# driver_board_v7.net
KiCad netlist of a schematic drawn in EAGLE
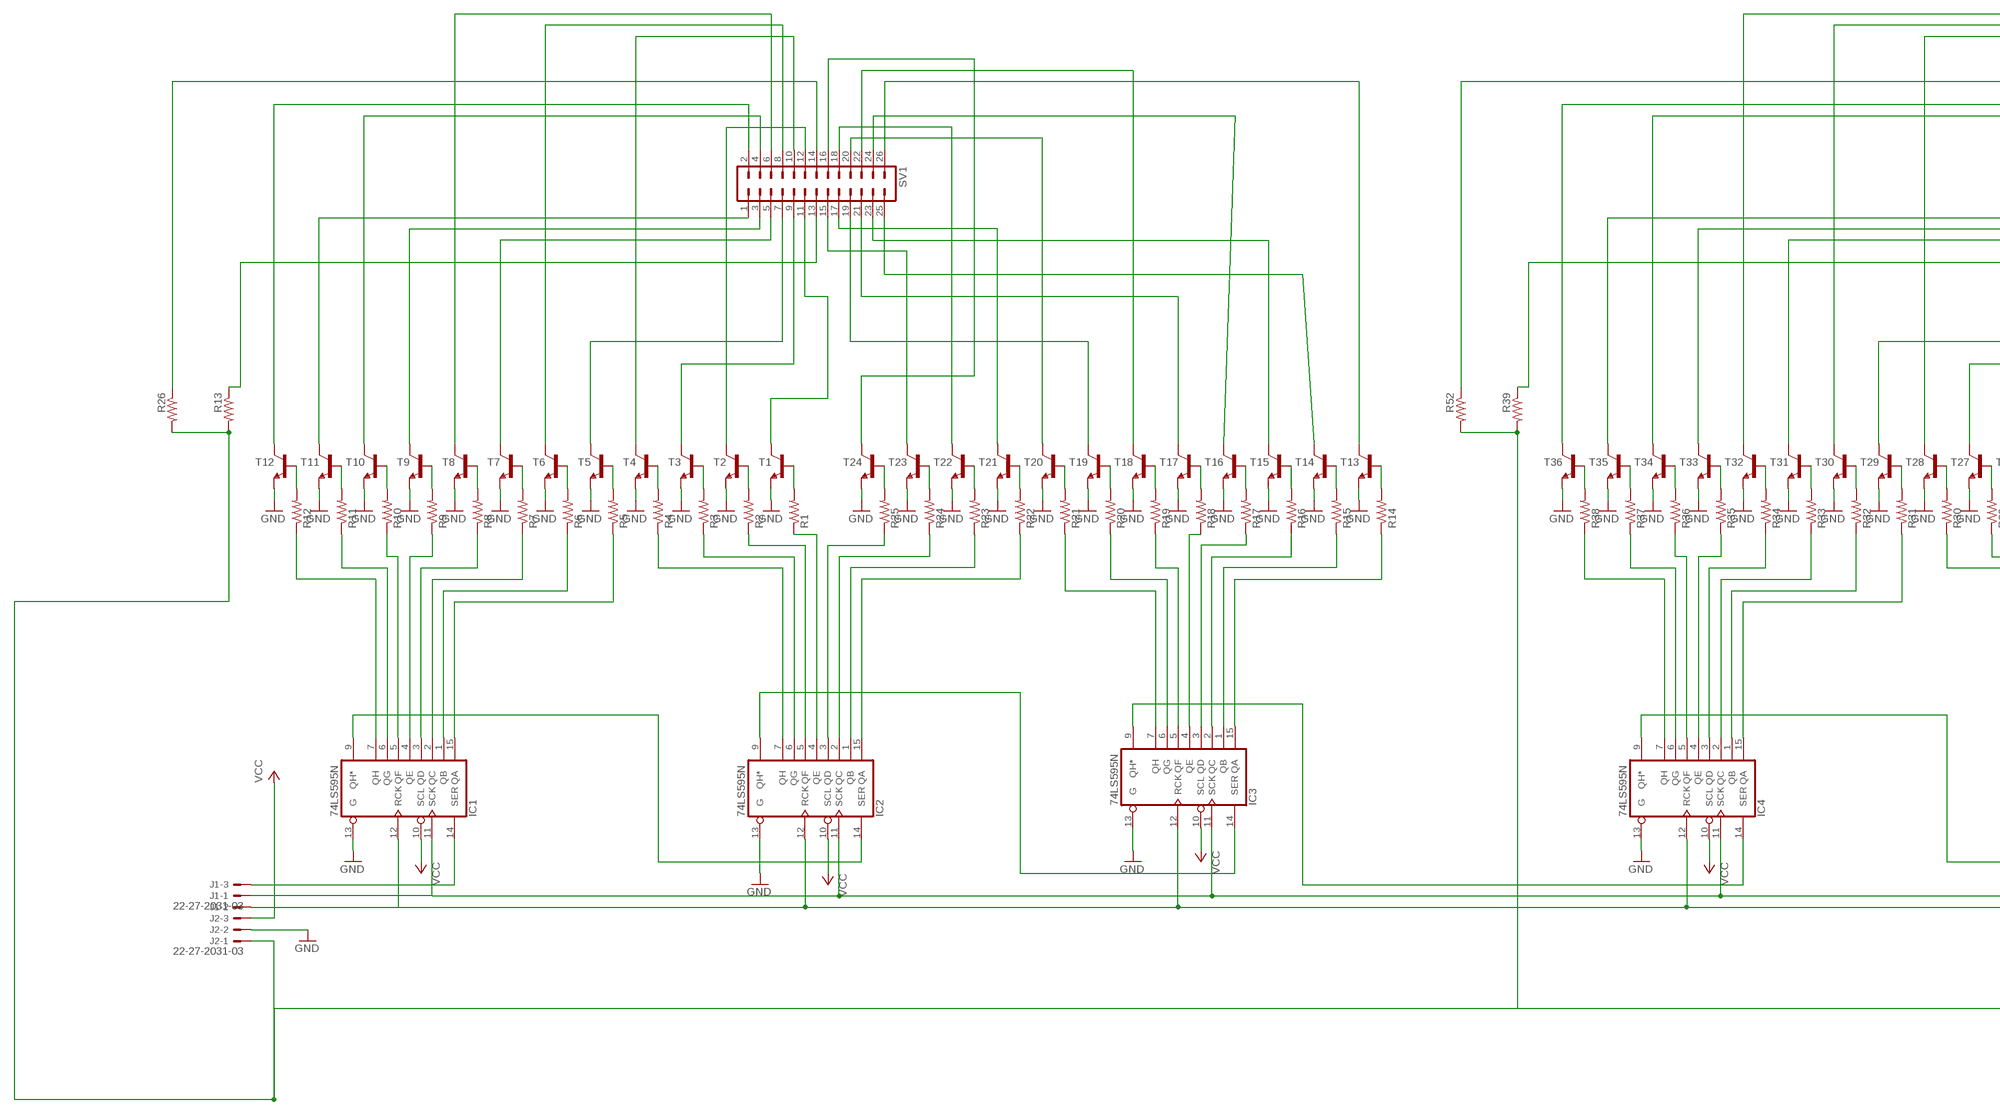
[diagram p0: schematic, sheet 1, part 1 of 2]
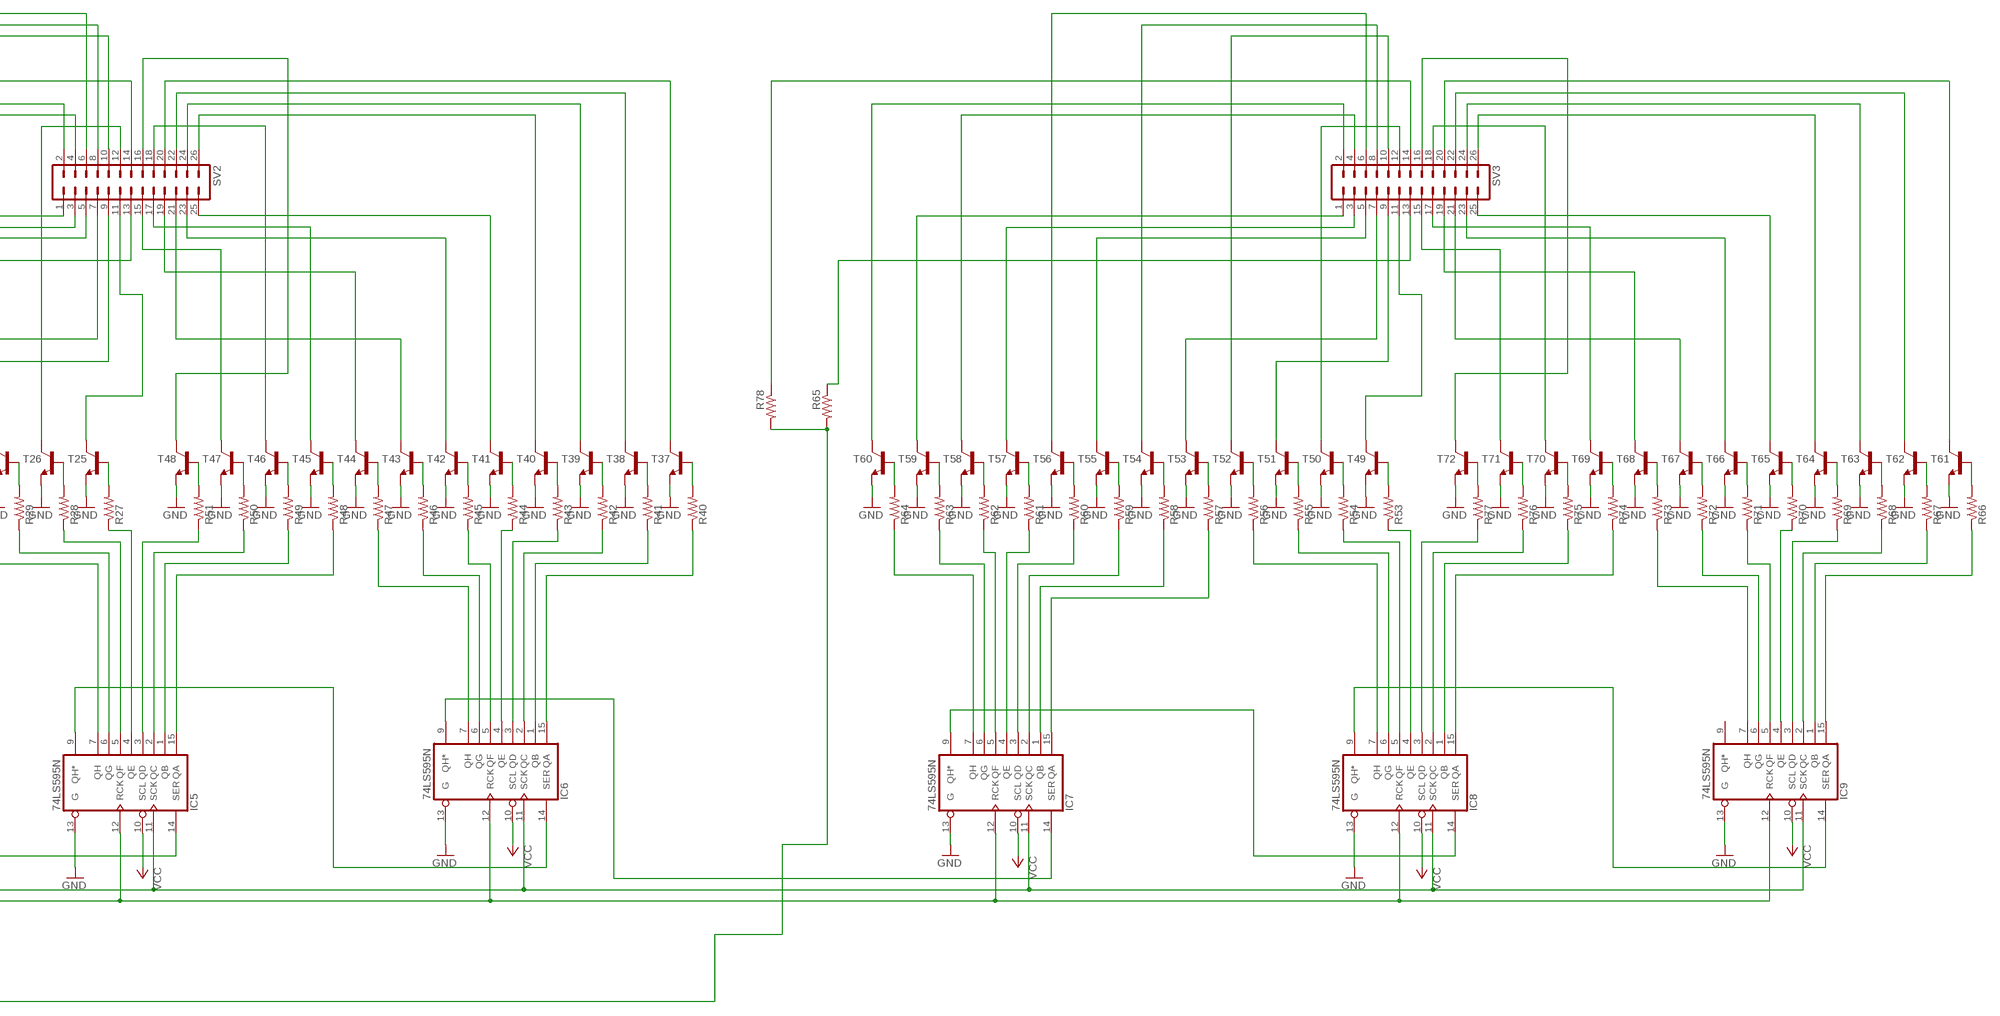
[diagram p1: schematic, sheet 1, part 2 of 2]

(export (version "E")
  (design (tool "Eeschema 10.0.6"))
  (components
    (comp (ref "IC1")
      (value "74LS595N")
      (footprint "eagle-import:DIL16")
      (libsource (lib "eagle-import") (part "74595NLS"))
    )
    (comp (ref "IC2")
      (value "74LS595N")
      (footprint "eagle-import:DIL16")
      (libsource (lib "eagle-import") (part "74595NLS"))
    )
    (comp (ref "IC3")
      (value "74LS595N")
      (footprint "eagle-import:DIL16")
      (libsource (lib "eagle-import") (part "74595NLS"))
    )
    (comp (ref "IC4")
      (value "74LS595N")
      (footprint "eagle-import:DIL16")
      (libsource (lib "eagle-import") (part "74595NLS"))
    )
    (comp (ref "IC5")
      (value "74LS595N")
      (footprint "eagle-import:DIL16")
      (libsource (lib "eagle-import") (part "74595NLS"))
    )
    (comp (ref "IC6")
      (value "74LS595N")
      (footprint "eagle-import:DIL16")
      (libsource (lib "eagle-import") (part "74595NLS"))
    )
    (comp (ref "IC7")
      (value "74LS595N")
      (footprint "eagle-import:DIL16")
      (libsource (lib "eagle-import") (part "74595NLS"))
    )
    (comp (ref "IC8")
      (value "74LS595N")
      (footprint "eagle-import:DIL16")
      (libsource (lib "eagle-import") (part "74595NLS"))
    )
    (comp (ref "IC9")
      (value "74LS595N")
      (footprint "eagle-import:DIL16")
      (libsource (lib "eagle-import") (part "74595NLS"))
    )
    (comp (ref "J1")
      (value "22-27-2031-03")
      (footprint "eagle-import:6410-03")
      (libsource (lib "eagle-import") (part "22-?-0327-2031"))
    )
    (comp (ref "J2")
      (value "22-27-2031-03")
      (footprint "eagle-import:6410-03")
      (libsource (lib "eagle-import") (part "22-?-0327-2031"))
    )
    (comp (ref "R1")
      (value "R-US_0204/7")
      (footprint "eagle-import:0204_7")
      (libsource (lib "eagle-import") (part "R-US_0204/7"))
    )
    (comp (ref "R2")
      (value "R-US_0204/7")
      (footprint "eagle-import:0204_7")
      (libsource (lib "eagle-import") (part "R-US_0204/7"))
    )
    (comp (ref "R3")
      (value "R-US_0204/7")
      (footprint "eagle-import:0204_7")
      (libsource (lib "eagle-import") (part "R-US_0204/7"))
    )
    (comp (ref "R4")
      (value "R-US_0204/7")
      (footprint "eagle-import:0204_7")
      (libsource (lib "eagle-import") (part "R-US_0204/7"))
    )
    (comp (ref "R5")
      (value "R-US_0204/7")
      (footprint "eagle-import:0204_7")
      (libsource (lib "eagle-import") (part "R-US_0204/7"))
    )
    (comp (ref "R6")
      (value "R-US_0204/7")
      (footprint "eagle-import:0204_7")
      (libsource (lib "eagle-import") (part "R-US_0204/7"))
    )
    (comp (ref "R7")
      (value "R-US_0204/7")
      (footprint "eagle-import:0204_7")
      (libsource (lib "eagle-import") (part "R-US_0204/7"))
    )
    (comp (ref "R8")
      (value "R-US_0204/7")
      (footprint "eagle-import:0204_7")
      (libsource (lib "eagle-import") (part "R-US_0204/7"))
    )
    (comp (ref "R9")
      (value "R-US_0204/7")
      (footprint "eagle-import:0204_7")
      (libsource (lib "eagle-import") (part "R-US_0204/7"))
    )
    (comp (ref "R10")
      (value "R-US_0204/7")
      (footprint "eagle-import:0204_7")
      (libsource (lib "eagle-import") (part "R-US_0204/7"))
    )
    (comp (ref "R11")
      (value "R-US_0204/7")
      (footprint "eagle-import:0204_7")
      (libsource (lib "eagle-import") (part "R-US_0204/7"))
    )
    (comp (ref "R12")
      (value "R-US_0204/7")
      (footprint "eagle-import:0204_7")
      (libsource (lib "eagle-import") (part "R-US_0204/7"))
    )
    (comp (ref "R13")
      (value "R-US_0204/7")
      (footprint "eagle-import:0204_7")
      (libsource (lib "eagle-import") (part "R-US_0204/7"))
    )
    (comp (ref "R14")
      (value "R-US_0204/7")
      (footprint "eagle-import:0204_7")
      (libsource (lib "eagle-import") (part "R-US_0204/7"))
    )
    (comp (ref "R15")
      (value "R-US_0204/7")
      (footprint "eagle-import:0204_7")
      (libsource (lib "eagle-import") (part "R-US_0204/7"))
    )
    (comp (ref "R16")
      (value "R-US_0204/7")
      (footprint "eagle-import:0204_7")
      (libsource (lib "eagle-import") (part "R-US_0204/7"))
    )
    (comp (ref "R17")
      (value "R-US_0204/7")
      (footprint "eagle-import:0204_7")
      (libsource (lib "eagle-import") (part "R-US_0204/7"))
    )
    (comp (ref "R18")
      (value "R-US_0204/7")
      (footprint "eagle-import:0204_7")
      (libsource (lib "eagle-import") (part "R-US_0204/7"))
    )
    (comp (ref "R19")
      (value "R-US_0204/7")
      (footprint "eagle-import:0204_7")
      (libsource (lib "eagle-import") (part "R-US_0204/7"))
    )
    (comp (ref "R20")
      (value "R-US_0204/7")
      (footprint "eagle-import:0204_7")
      (libsource (lib "eagle-import") (part "R-US_0204/7"))
    )
    (comp (ref "R21")
      (value "R-US_0204/7")
      (footprint "eagle-import:0204_7")
      (libsource (lib "eagle-import") (part "R-US_0204/7"))
    )
    (comp (ref "R22")
      (value "R-US_0204/7")
      (footprint "eagle-import:0204_7")
      (libsource (lib "eagle-import") (part "R-US_0204/7"))
    )
    (comp (ref "R23")
      (value "R-US_0204/7")
      (footprint "eagle-import:0204_7")
      (libsource (lib "eagle-import") (part "R-US_0204/7"))
    )
    (comp (ref "R24")
      (value "R-US_0204/7")
      (footprint "eagle-import:0204_7")
      (libsource (lib "eagle-import") (part "R-US_0204/7"))
    )
    (comp (ref "R25")
      (value "R-US_0204/7")
      (footprint "eagle-import:0204_7")
      (libsource (lib "eagle-import") (part "R-US_0204/7"))
    )
    (comp (ref "R26")
      (value "R-US_0204/7")
      (footprint "eagle-import:0204_7")
      (libsource (lib "eagle-import") (part "R-US_0204/7"))
    )
    (comp (ref "R27")
      (value "R-US_0204/7")
      (footprint "eagle-import:0204_7")
      (libsource (lib "eagle-import") (part "R-US_0204/7"))
    )
    (comp (ref "R28")
      (value "R-US_0204/7")
      (footprint "eagle-import:0204_7")
      (libsource (lib "eagle-import") (part "R-US_0204/7"))
    )
    (comp (ref "R29")
      (value "R-US_0204/7")
      (footprint "eagle-import:0204_7")
      (libsource (lib "eagle-import") (part "R-US_0204/7"))
    )
    (comp (ref "R30")
      (value "R-US_0204/7")
      (footprint "eagle-import:0204_7")
      (libsource (lib "eagle-import") (part "R-US_0204/7"))
    )
    (comp (ref "R31")
      (value "R-US_0204/7")
      (footprint "eagle-import:0204_7")
      (libsource (lib "eagle-import") (part "R-US_0204/7"))
    )
    (comp (ref "R32")
      (value "R-US_0204/7")
      (footprint "eagle-import:0204_7")
      (libsource (lib "eagle-import") (part "R-US_0204/7"))
    )
    (comp (ref "R33")
      (value "R-US_0204/7")
      (footprint "eagle-import:0204_7")
      (libsource (lib "eagle-import") (part "R-US_0204/7"))
    )
    (comp (ref "R34")
      (value "R-US_0204/7")
      (footprint "eagle-import:0204_7")
      (libsource (lib "eagle-import") (part "R-US_0204/7"))
    )
    (comp (ref "R35")
      (value "R-US_0204/7")
      (footprint "eagle-import:0204_7")
      (libsource (lib "eagle-import") (part "R-US_0204/7"))
    )
    (comp (ref "R36")
      (value "R-US_0204/7")
      (footprint "eagle-import:0204_7")
      (libsource (lib "eagle-import") (part "R-US_0204/7"))
    )
    (comp (ref "R37")
      (value "R-US_0204/7")
      (footprint "eagle-import:0204_7")
      (libsource (lib "eagle-import") (part "R-US_0204/7"))
    )
    (comp (ref "R38")
      (value "R-US_0204/7")
      (footprint "eagle-import:0204_7")
      (libsource (lib "eagle-import") (part "R-US_0204/7"))
    )
    (comp (ref "R39")
      (value "R-US_0204/7")
      (footprint "eagle-import:0204_7")
      (libsource (lib "eagle-import") (part "R-US_0204/7"))
    )
    (comp (ref "R40")
      (value "R-US_0204/7")
      (footprint "eagle-import:0204_7")
      (libsource (lib "eagle-import") (part "R-US_0204/7"))
    )
    (comp (ref "R41")
      (value "R-US_0204/7")
      (footprint "eagle-import:0204_7")
      (libsource (lib "eagle-import") (part "R-US_0204/7"))
    )
    (comp (ref "R42")
      (value "R-US_0204/7")
      (footprint "eagle-import:0204_7")
      (libsource (lib "eagle-import") (part "R-US_0204/7"))
    )
    (comp (ref "R43")
      (value "R-US_0204/7")
      (footprint "eagle-import:0204_7")
      (libsource (lib "eagle-import") (part "R-US_0204/7"))
    )
    (comp (ref "R44")
      (value "R-US_0204/7")
      (footprint "eagle-import:0204_7")
      (libsource (lib "eagle-import") (part "R-US_0204/7"))
    )
    (comp (ref "R45")
      (value "R-US_0204/7")
      (footprint "eagle-import:0204_7")
      (libsource (lib "eagle-import") (part "R-US_0204/7"))
    )
    (comp (ref "R46")
      (value "R-US_0204/7")
      (footprint "eagle-import:0204_7")
      (libsource (lib "eagle-import") (part "R-US_0204/7"))
    )
    (comp (ref "R47")
      (value "R-US_0204/7")
      (footprint "eagle-import:0204_7")
      (libsource (lib "eagle-import") (part "R-US_0204/7"))
    )
    (comp (ref "R48")
      (value "R-US_0204/7")
      (footprint "eagle-import:0204_7")
      (libsource (lib "eagle-import") (part "R-US_0204/7"))
    )
    (comp (ref "R49")
      (value "R-US_0204/7")
      (footprint "eagle-import:0204_7")
      (libsource (lib "eagle-import") (part "R-US_0204/7"))
    )
    (comp (ref "R50")
      (value "R-US_0204/7")
      (footprint "eagle-import:0204_7")
      (libsource (lib "eagle-import") (part "R-US_0204/7"))
    )
    (comp (ref "R51")
      (value "R-US_0204/7")
      (footprint "eagle-import:0204_7")
      (libsource (lib "eagle-import") (part "R-US_0204/7"))
    )
    (comp (ref "R52")
      (value "R-US_0204/7")
      (footprint "eagle-import:0204_7")
      (libsource (lib "eagle-import") (part "R-US_0204/7"))
    )
    (comp (ref "R53")
      (value "R-US_0204/7")
      (footprint "eagle-import:0204_7")
      (libsource (lib "eagle-import") (part "R-US_0204/7"))
    )
    (comp (ref "R54")
      (value "R-US_0204/7")
      (footprint "eagle-import:0204_7")
      (libsource (lib "eagle-import") (part "R-US_0204/7"))
    )
    (comp (ref "R55")
      (value "R-US_0204/7")
      (footprint "eagle-import:0204_7")
      (libsource (lib "eagle-import") (part "R-US_0204/7"))
    )
    (comp (ref "R56")
      (value "R-US_0204/7")
      (footprint "eagle-import:0204_7")
      (libsource (lib "eagle-import") (part "R-US_0204/7"))
    )
    (comp (ref "R57")
      (value "R-US_0204/7")
      (footprint "eagle-import:0204_7")
      (libsource (lib "eagle-import") (part "R-US_0204/7"))
    )
    (comp (ref "R58")
      (value "R-US_0204/7")
      (footprint "eagle-import:0204_7")
      (libsource (lib "eagle-import") (part "R-US_0204/7"))
    )
    (comp (ref "R59")
      (value "R-US_0204/7")
      (footprint "eagle-import:0204_7")
      (libsource (lib "eagle-import") (part "R-US_0204/7"))
    )
    (comp (ref "R60")
      (value "R-US_0204/7")
      (footprint "eagle-import:0204_7")
      (libsource (lib "eagle-import") (part "R-US_0204/7"))
    )
    (comp (ref "R61")
      (value "R-US_0204/7")
      (footprint "eagle-import:0204_7")
      (libsource (lib "eagle-import") (part "R-US_0204/7"))
    )
    (comp (ref "R62")
      (value "R-US_0204/7")
      (footprint "eagle-import:0204_7")
      (libsource (lib "eagle-import") (part "R-US_0204/7"))
    )
    (comp (ref "R63")
      (value "R-US_0204/7")
      (footprint "eagle-import:0204_7")
      (libsource (lib "eagle-import") (part "R-US_0204/7"))
    )
    (comp (ref "R64")
      (value "R-US_0204/7")
      (footprint "eagle-import:0204_7")
      (libsource (lib "eagle-import") (part "R-US_0204/7"))
    )
    (comp (ref "R65")
      (value "R-US_0204/7")
      (footprint "eagle-import:0204_7")
      (libsource (lib "eagle-import") (part "R-US_0204/7"))
    )
    (comp (ref "R66")
      (value "R-US_0204/7")
      (footprint "eagle-import:0204_7")
      (libsource (lib "eagle-import") (part "R-US_0204/7"))
    )
    (comp (ref "R67")
      (value "R-US_0204/7")
      (footprint "eagle-import:0204_7")
      (libsource (lib "eagle-import") (part "R-US_0204/7"))
    )
    (comp (ref "R68")
      (value "R-US_0204/7")
      (footprint "eagle-import:0204_7")
      (libsource (lib "eagle-import") (part "R-US_0204/7"))
    )
    (comp (ref "R69")
      (value "R-US_0204/7")
      (footprint "eagle-import:0204_7")
      (libsource (lib "eagle-import") (part "R-US_0204/7"))
    )
    (comp (ref "R70")
      (value "R-US_0204/7")
      (footprint "eagle-import:0204_7")
      (libsource (lib "eagle-import") (part "R-US_0204/7"))
    )
    (comp (ref "R71")
      (value "R-US_0204/7")
      (footprint "eagle-import:0204_7")
      (libsource (lib "eagle-import") (part "R-US_0204/7"))
    )
    (comp (ref "R72")
      (value "R-US_0204/7")
      (footprint "eagle-import:0204_7")
      (libsource (lib "eagle-import") (part "R-US_0204/7"))
    )
    (comp (ref "R73")
      (value "R-US_0204/7")
      (footprint "eagle-import:0204_7")
      (libsource (lib "eagle-import") (part "R-US_0204/7"))
    )
    (comp (ref "R74")
      (value "R-US_0204/7")
      (footprint "eagle-import:0204_7")
      (libsource (lib "eagle-import") (part "R-US_0204/7"))
    )
    (comp (ref "R75")
      (value "R-US_0204/7")
      (footprint "eagle-import:0204_7")
      (libsource (lib "eagle-import") (part "R-US_0204/7"))
    )
    (comp (ref "R76")
      (value "R-US_0204/7")
      (footprint "eagle-import:0204_7")
      (libsource (lib "eagle-import") (part "R-US_0204/7"))
    )
    (comp (ref "R77")
      (value "R-US_0204/7")
      (footprint "eagle-import:0204_7")
      (libsource (lib "eagle-import") (part "R-US_0204/7"))
    )
    (comp (ref "R78")
      (value "R-US_0204/7")
      (footprint "eagle-import:0204_7")
      (libsource (lib "eagle-import") (part "R-US_0204/7"))
    )
    (comp (ref "SV1")
      (value "MA13-2")
      (footprint "eagle-import:MA13-2")
      (libsource (lib "eagle-import") (part "MA13-2"))
    )
    (comp (ref "SV2")
      (value "MA13-2")
      (footprint "eagle-import:MA13-2")
      (libsource (lib "eagle-import") (part "MA13-2"))
    )
    (comp (ref "SV3")
      (value "MA13-2")
      (footprint "eagle-import:MA13-2")
      (libsource (lib "eagle-import") (part "MA13-2"))
    )
    (comp (ref "T1")
      (value "29-NPN-TO92-EBC")
      (footprint "eagle-import:TO92-EBC")
      (libsource (lib "eagle-import") (part "-NPN-TO92-EBC29"))
    )
    (comp (ref "T2")
      (value "29-NPN-TO92-EBC")
      (footprint "eagle-import:TO92-EBC")
      (libsource (lib "eagle-import") (part "-NPN-TO92-EBC29"))
    )
    (comp (ref "T3")
      (value "29-NPN-TO92-EBC")
      (footprint "eagle-import:TO92-EBC")
      (libsource (lib "eagle-import") (part "-NPN-TO92-EBC29"))
    )
    (comp (ref "T4")
      (value "29-NPN-TO92-EBC")
      (footprint "eagle-import:TO92-EBC")
      (libsource (lib "eagle-import") (part "-NPN-TO92-EBC29"))
    )
    (comp (ref "T5")
      (value "29-NPN-TO92-EBC")
      (footprint "eagle-import:TO92-EBC")
      (libsource (lib "eagle-import") (part "-NPN-TO92-EBC29"))
    )
    (comp (ref "T6")
      (value "29-NPN-TO92-EBC")
      (footprint "eagle-import:TO92-EBC")
      (libsource (lib "eagle-import") (part "-NPN-TO92-EBC29"))
    )
    (comp (ref "T7")
      (value "29-NPN-TO92-EBC")
      (footprint "eagle-import:TO92-EBC")
      (libsource (lib "eagle-import") (part "-NPN-TO92-EBC29"))
    )
    (comp (ref "T8")
      (value "29-NPN-TO92-EBC")
      (footprint "eagle-import:TO92-EBC")
      (libsource (lib "eagle-import") (part "-NPN-TO92-EBC29"))
    )
    (comp (ref "T9")
      (value "29-NPN-TO92-EBC")
      (footprint "eagle-import:TO92-EBC")
      (libsource (lib "eagle-import") (part "-NPN-TO92-EBC29"))
    )
    (comp (ref "T10")
      (value "29-NPN-TO92-EBC")
      (footprint "eagle-import:TO92-EBC")
      (libsource (lib "eagle-import") (part "-NPN-TO92-EBC29"))
    )
    (comp (ref "T11")
      (value "29-NPN-TO92-EBC")
      (footprint "eagle-import:TO92-EBC")
      (libsource (lib "eagle-import") (part "-NPN-TO92-EBC29"))
    )
    (comp (ref "T12")
      (value "29-NPN-TO92-EBC")
      (footprint "eagle-import:TO92-EBC")
      (libsource (lib "eagle-import") (part "-NPN-TO92-EBC29"))
    )
    (comp (ref "T13")
      (value "29-NPN-TO92-EBC")
      (footprint "eagle-import:TO92-EBC")
      (libsource (lib "eagle-import") (part "-NPN-TO92-EBC29"))
    )
    (comp (ref "T14")
      (value "29-NPN-TO92-EBC")
      (footprint "eagle-import:TO92-EBC")
      (libsource (lib "eagle-import") (part "-NPN-TO92-EBC29"))
    )
    (comp (ref "T15")
      (value "29-NPN-TO92-EBC")
      (footprint "eagle-import:TO92-EBC")
      (libsource (lib "eagle-import") (part "-NPN-TO92-EBC29"))
    )
    (comp (ref "T16")
      (value "29-NPN-TO92-EBC")
      (footprint "eagle-import:TO92-EBC")
      (libsource (lib "eagle-import") (part "-NPN-TO92-EBC29"))
    )
    (comp (ref "T17")
      (value "29-NPN-TO92-EBC")
      (footprint "eagle-import:TO92-EBC")
      (libsource (lib "eagle-import") (part "-NPN-TO92-EBC29"))
    )
    (comp (ref "T18")
      (value "29-NPN-TO92-EBC")
      (footprint "eagle-import:TO92-EBC")
      (libsource (lib "eagle-import") (part "-NPN-TO92-EBC29"))
    )
    (comp (ref "T19")
      (value "29-NPN-TO92-EBC")
      (footprint "eagle-import:TO92-EBC")
      (libsource (lib "eagle-import") (part "-NPN-TO92-EBC29"))
    )
    (comp (ref "T20")
      (value "29-NPN-TO92-EBC")
      (footprint "eagle-import:TO92-EBC")
      (libsource (lib "eagle-import") (part "-NPN-TO92-EBC29"))
    )
    (comp (ref "T21")
      (value "29-NPN-TO92-EBC")
      (footprint "eagle-import:TO92-EBC")
      (libsource (lib "eagle-import") (part "-NPN-TO92-EBC29"))
    )
    (comp (ref "T22")
      (value "29-NPN-TO92-EBC")
      (footprint "eagle-import:TO92-EBC")
      (libsource (lib "eagle-import") (part "-NPN-TO92-EBC29"))
    )
    (comp (ref "T23")
      (value "29-NPN-TO92-EBC")
      (footprint "eagle-import:TO92-EBC")
      (libsource (lib "eagle-import") (part "-NPN-TO92-EBC29"))
    )
    (comp (ref "T24")
      (value "29-NPN-TO92-EBC")
      (footprint "eagle-import:TO92-EBC")
      (libsource (lib "eagle-import") (part "-NPN-TO92-EBC29"))
    )
    (comp (ref "T25")
      (value "29-NPN-TO92-EBC")
      (footprint "eagle-import:TO92-EBC")
      (libsource (lib "eagle-import") (part "-NPN-TO92-EBC29"))
    )
    (comp (ref "T26")
      (value "29-NPN-TO92-EBC")
      (footprint "eagle-import:TO92-EBC")
      (libsource (lib "eagle-import") (part "-NPN-TO92-EBC29"))
    )
    (comp (ref "T27")
      (value "29-NPN-TO92-EBC")
      (footprint "eagle-import:TO92-EBC")
      (libsource (lib "eagle-import") (part "-NPN-TO92-EBC29"))
    )
    (comp (ref "T28")
      (value "29-NPN-TO92-EBC")
      (footprint "eagle-import:TO92-EBC")
      (libsource (lib "eagle-import") (part "-NPN-TO92-EBC29"))
    )
    (comp (ref "T29")
      (value "29-NPN-TO92-EBC")
      (footprint "eagle-import:TO92-EBC")
      (libsource (lib "eagle-import") (part "-NPN-TO92-EBC29"))
    )
    (comp (ref "T30")
      (value "29-NPN-TO92-EBC")
      (footprint "eagle-import:TO92-EBC")
      (libsource (lib "eagle-import") (part "-NPN-TO92-EBC29"))
    )
    (comp (ref "T31")
      (value "29-NPN-TO92-EBC")
      (footprint "eagle-import:TO92-EBC")
      (libsource (lib "eagle-import") (part "-NPN-TO92-EBC29"))
    )
    (comp (ref "T32")
      (value "29-NPN-TO92-EBC")
      (footprint "eagle-import:TO92-EBC")
      (libsource (lib "eagle-import") (part "-NPN-TO92-EBC29"))
    )
    (comp (ref "T33")
      (value "29-NPN-TO92-EBC")
      (footprint "eagle-import:TO92-EBC")
      (libsource (lib "eagle-import") (part "-NPN-TO92-EBC29"))
    )
    (comp (ref "T34")
      (value "29-NPN-TO92-EBC")
      (footprint "eagle-import:TO92-EBC")
      (libsource (lib "eagle-import") (part "-NPN-TO92-EBC29"))
    )
    (comp (ref "T35")
      (value "29-NPN-TO92-EBC")
      (footprint "eagle-import:TO92-EBC")
      (libsource (lib "eagle-import") (part "-NPN-TO92-EBC29"))
    )
    (comp (ref "T36")
      (value "29-NPN-TO92-EBC")
      (footprint "eagle-import:TO92-EBC")
      (libsource (lib "eagle-import") (part "-NPN-TO92-EBC29"))
    )
    (comp (ref "T37")
      (value "29-NPN-TO92-EBC")
      (footprint "eagle-import:TO92-EBC")
      (libsource (lib "eagle-import") (part "-NPN-TO92-EBC29"))
    )
    (comp (ref "T38")
      (value "29-NPN-TO92-EBC")
      (footprint "eagle-import:TO92-EBC")
      (libsource (lib "eagle-import") (part "-NPN-TO92-EBC29"))
    )
    (comp (ref "T39")
      (value "29-NPN-TO92-EBC")
      (footprint "eagle-import:TO92-EBC")
      (libsource (lib "eagle-import") (part "-NPN-TO92-EBC29"))
    )
    (comp (ref "T40")
      (value "29-NPN-TO92-EBC")
      (footprint "eagle-import:TO92-EBC")
      (libsource (lib "eagle-import") (part "-NPN-TO92-EBC29"))
    )
    (comp (ref "T41")
      (value "29-NPN-TO92-EBC")
      (footprint "eagle-import:TO92-EBC")
      (libsource (lib "eagle-import") (part "-NPN-TO92-EBC29"))
    )
    (comp (ref "T42")
      (value "29-NPN-TO92-EBC")
      (footprint "eagle-import:TO92-EBC")
      (libsource (lib "eagle-import") (part "-NPN-TO92-EBC29"))
    )
    (comp (ref "T43")
      (value "29-NPN-TO92-EBC")
      (footprint "eagle-import:TO92-EBC")
      (libsource (lib "eagle-import") (part "-NPN-TO92-EBC29"))
    )
    (comp (ref "T44")
      (value "29-NPN-TO92-EBC")
      (footprint "eagle-import:TO92-EBC")
      (libsource (lib "eagle-import") (part "-NPN-TO92-EBC29"))
    )
    (comp (ref "T45")
      (value "29-NPN-TO92-EBC")
      (footprint "eagle-import:TO92-EBC")
      (libsource (lib "eagle-import") (part "-NPN-TO92-EBC29"))
    )
    (comp (ref "T46")
      (value "29-NPN-TO92-EBC")
      (footprint "eagle-import:TO92-EBC")
      (libsource (lib "eagle-import") (part "-NPN-TO92-EBC29"))
    )
    (comp (ref "T47")
      (value "29-NPN-TO92-EBC")
      (footprint "eagle-import:TO92-EBC")
      (libsource (lib "eagle-import") (part "-NPN-TO92-EBC29"))
    )
    (comp (ref "T48")
      (value "29-NPN-TO92-EBC")
      (footprint "eagle-import:TO92-EBC")
      (libsource (lib "eagle-import") (part "-NPN-TO92-EBC29"))
    )
    (comp (ref "T49")
      (value "29-NPN-TO92-EBC")
      (footprint "eagle-import:TO92-EBC")
      (libsource (lib "eagle-import") (part "-NPN-TO92-EBC29"))
    )
    (comp (ref "T50")
      (value "29-NPN-TO92-EBC")
      (footprint "eagle-import:TO92-EBC")
      (libsource (lib "eagle-import") (part "-NPN-TO92-EBC29"))
    )
    (comp (ref "T51")
      (value "29-NPN-TO92-EBC")
      (footprint "eagle-import:TO92-EBC")
      (libsource (lib "eagle-import") (part "-NPN-TO92-EBC29"))
    )
    (comp (ref "T52")
      (value "29-NPN-TO92-EBC")
      (footprint "eagle-import:TO92-EBC")
      (libsource (lib "eagle-import") (part "-NPN-TO92-EBC29"))
    )
    (comp (ref "T53")
      (value "29-NPN-TO92-EBC")
      (footprint "eagle-import:TO92-EBC")
      (libsource (lib "eagle-import") (part "-NPN-TO92-EBC29"))
    )
    (comp (ref "T54")
      (value "29-NPN-TO92-EBC")
      (footprint "eagle-import:TO92-EBC")
      (libsource (lib "eagle-import") (part "-NPN-TO92-EBC29"))
    )
    (comp (ref "T55")
      (value "29-NPN-TO92-EBC")
      (footprint "eagle-import:TO92-EBC")
      (libsource (lib "eagle-import") (part "-NPN-TO92-EBC29"))
    )
    (comp (ref "T56")
      (value "29-NPN-TO92-EBC")
      (footprint "eagle-import:TO92-EBC")
      (libsource (lib "eagle-import") (part "-NPN-TO92-EBC29"))
    )
    (comp (ref "T57")
      (value "29-NPN-TO92-EBC")
      (footprint "eagle-import:TO92-EBC")
      (libsource (lib "eagle-import") (part "-NPN-TO92-EBC29"))
    )
    (comp (ref "T58")
      (value "29-NPN-TO92-EBC")
      (footprint "eagle-import:TO92-EBC")
      (libsource (lib "eagle-import") (part "-NPN-TO92-EBC29"))
    )
    (comp (ref "T59")
      (value "29-NPN-TO92-EBC")
      (footprint "eagle-import:TO92-EBC")
      (libsource (lib "eagle-import") (part "-NPN-TO92-EBC29"))
    )
    (comp (ref "T60")
      (value "29-NPN-TO92-EBC")
      (footprint "eagle-import:TO92-EBC")
      (libsource (lib "eagle-import") (part "-NPN-TO92-EBC29"))
    )
    (comp (ref "T61")
      (value "29-NPN-TO92-EBC")
      (footprint "eagle-import:TO92-EBC")
      (libsource (lib "eagle-import") (part "-NPN-TO92-EBC29"))
    )
    (comp (ref "T62")
      (value "29-NPN-TO92-EBC")
      (footprint "eagle-import:TO92-EBC")
      (libsource (lib "eagle-import") (part "-NPN-TO92-EBC29"))
    )
    (comp (ref "T63")
      (value "29-NPN-TO92-EBC")
      (footprint "eagle-import:TO92-EBC")
      (libsource (lib "eagle-import") (part "-NPN-TO92-EBC29"))
    )
    (comp (ref "T64")
      (value "29-NPN-TO92-EBC")
      (footprint "eagle-import:TO92-EBC")
      (libsource (lib "eagle-import") (part "-NPN-TO92-EBC29"))
    )
    (comp (ref "T65")
      (value "29-NPN-TO92-EBC")
      (footprint "eagle-import:TO92-EBC")
      (libsource (lib "eagle-import") (part "-NPN-TO92-EBC29"))
    )
    (comp (ref "T66")
      (value "29-NPN-TO92-EBC")
      (footprint "eagle-import:TO92-EBC")
      (libsource (lib "eagle-import") (part "-NPN-TO92-EBC29"))
    )
    (comp (ref "T67")
      (value "29-NPN-TO92-EBC")
      (footprint "eagle-import:TO92-EBC")
      (libsource (lib "eagle-import") (part "-NPN-TO92-EBC29"))
    )
    (comp (ref "T68")
      (value "29-NPN-TO92-EBC")
      (footprint "eagle-import:TO92-EBC")
      (libsource (lib "eagle-import") (part "-NPN-TO92-EBC29"))
    )
    (comp (ref "T69")
      (value "29-NPN-TO92-EBC")
      (footprint "eagle-import:TO92-EBC")
      (libsource (lib "eagle-import") (part "-NPN-TO92-EBC29"))
    )
    (comp (ref "T70")
      (value "29-NPN-TO92-EBC")
      (footprint "eagle-import:TO92-EBC")
      (libsource (lib "eagle-import") (part "-NPN-TO92-EBC29"))
    )
    (comp (ref "T71")
      (value "29-NPN-TO92-EBC")
      (footprint "eagle-import:TO92-EBC")
      (libsource (lib "eagle-import") (part "-NPN-TO92-EBC29"))
    )
    (comp (ref "T72")
      (value "29-NPN-TO92-EBC")
      (footprint "eagle-import:TO92-EBC")
      (libsource (lib "eagle-import") (part "-NPN-TO92-EBC29"))
    )
  )
  (nets
    (net (code "1") (name "GND") (class "Default")
      (node (ref "IC1") (pin "13") (pinfunction "G_13") (pintype "input"))
      (node (ref "IC2") (pin "13") (pinfunction "G_13") (pintype "input"))
      (node (ref "IC3") (pin "13") (pinfunction "G_13") (pintype "input"))
      (node (ref "IC4") (pin "13") (pinfunction "G_13") (pintype "input"))
      (node (ref "IC5") (pin "13") (pinfunction "G_13") (pintype "input"))
      (node (ref "IC6") (pin "13") (pinfunction "G_13") (pintype "input"))
      (node (ref "IC7") (pin "13") (pinfunction "G_13") (pintype "input"))
      (node (ref "IC8") (pin "13") (pinfunction "G_13") (pintype "input"))
      (node (ref "IC9") (pin "13") (pinfunction "G_13") (pintype "input"))
      (node (ref "J2") (pin "2") (pinfunction "S_2") (pintype "passive"))
      (node (ref "T1") (pin "E") (pinfunction "E_E") (pintype "passive"))
      (node (ref "T10") (pin "E") (pinfunction "E_E") (pintype "passive"))
      (node (ref "T11") (pin "E") (pinfunction "E_E") (pintype "passive"))
      (node (ref "T12") (pin "E") (pinfunction "E_E") (pintype "passive"))
      (node (ref "T13") (pin "E") (pinfunction "E_E") (pintype "passive"))
      (node (ref "T14") (pin "E") (pinfunction "E_E") (pintype "passive"))
      (node (ref "T15") (pin "E") (pinfunction "E_E") (pintype "passive"))
      (node (ref "T16") (pin "E") (pinfunction "E_E") (pintype "passive"))
      (node (ref "T17") (pin "E") (pinfunction "E_E") (pintype "passive"))
      (node (ref "T18") (pin "E") (pinfunction "E_E") (pintype "passive"))
      (node (ref "T19") (pin "E") (pinfunction "E_E") (pintype "passive"))
      (node (ref "T2") (pin "E") (pinfunction "E_E") (pintype "passive"))
      (node (ref "T20") (pin "E") (pinfunction "E_E") (pintype "passive"))
      (node (ref "T21") (pin "E") (pinfunction "E_E") (pintype "passive"))
      (node (ref "T22") (pin "E") (pinfunction "E_E") (pintype "passive"))
      (node (ref "T23") (pin "E") (pinfunction "E_E") (pintype "passive"))
      (node (ref "T24") (pin "E") (pinfunction "E_E") (pintype "passive"))
      (node (ref "T25") (pin "E") (pinfunction "E_E") (pintype "passive"))
      (node (ref "T26") (pin "E") (pinfunction "E_E") (pintype "passive"))
      (node (ref "T27") (pin "E") (pinfunction "E_E") (pintype "passive"))
      (node (ref "T28") (pin "E") (pinfunction "E_E") (pintype "passive"))
      (node (ref "T29") (pin "E") (pinfunction "E_E") (pintype "passive"))
      (node (ref "T3") (pin "E") (pinfunction "E_E") (pintype "passive"))
      (node (ref "T30") (pin "E") (pinfunction "E_E") (pintype "passive"))
      (node (ref "T31") (pin "E") (pinfunction "E_E") (pintype "passive"))
      (node (ref "T32") (pin "E") (pinfunction "E_E") (pintype "passive"))
      (node (ref "T33") (pin "E") (pinfunction "E_E") (pintype "passive"))
      (node (ref "T34") (pin "E") (pinfunction "E_E") (pintype "passive"))
      (node (ref "T35") (pin "E") (pinfunction "E_E") (pintype "passive"))
      (node (ref "T36") (pin "E") (pinfunction "E_E") (pintype "passive"))
      (node (ref "T37") (pin "E") (pinfunction "E_E") (pintype "passive"))
      (node (ref "T38") (pin "E") (pinfunction "E_E") (pintype "passive"))
      (node (ref "T39") (pin "E") (pinfunction "E_E") (pintype "passive"))
      (node (ref "T4") (pin "E") (pinfunction "E_E") (pintype "passive"))
      (node (ref "T40") (pin "E") (pinfunction "E_E") (pintype "passive"))
      (node (ref "T41") (pin "E") (pinfunction "E_E") (pintype "passive"))
      (node (ref "T42") (pin "E") (pinfunction "E_E") (pintype "passive"))
      (node (ref "T43") (pin "E") (pinfunction "E_E") (pintype "passive"))
      (node (ref "T44") (pin "E") (pinfunction "E_E") (pintype "passive"))
      (node (ref "T45") (pin "E") (pinfunction "E_E") (pintype "passive"))
      (node (ref "T46") (pin "E") (pinfunction "E_E") (pintype "passive"))
      (node (ref "T47") (pin "E") (pinfunction "E_E") (pintype "passive"))
      (node (ref "T48") (pin "E") (pinfunction "E_E") (pintype "passive"))
      (node (ref "T49") (pin "E") (pinfunction "E_E") (pintype "passive"))
      (node (ref "T5") (pin "E") (pinfunction "E_E") (pintype "passive"))
      (node (ref "T50") (pin "E") (pinfunction "E_E") (pintype "passive"))
      (node (ref "T51") (pin "E") (pinfunction "E_E") (pintype "passive"))
      (node (ref "T52") (pin "E") (pinfunction "E_E") (pintype "passive"))
      (node (ref "T53") (pin "E") (pinfunction "E_E") (pintype "passive"))
      (node (ref "T54") (pin "E") (pinfunction "E_E") (pintype "passive"))
      (node (ref "T55") (pin "E") (pinfunction "E_E") (pintype "passive"))
      (node (ref "T56") (pin "E") (pinfunction "E_E") (pintype "passive"))
      (node (ref "T57") (pin "E") (pinfunction "E_E") (pintype "passive"))
      (node (ref "T58") (pin "E") (pinfunction "E_E") (pintype "passive"))
      (node (ref "T59") (pin "E") (pinfunction "E_E") (pintype "passive"))
      (node (ref "T6") (pin "E") (pinfunction "E_E") (pintype "passive"))
      (node (ref "T60") (pin "E") (pinfunction "E_E") (pintype "passive"))
      (node (ref "T61") (pin "E") (pinfunction "E_E") (pintype "passive"))
      (node (ref "T62") (pin "E") (pinfunction "E_E") (pintype "passive"))
      (node (ref "T63") (pin "E") (pinfunction "E_E") (pintype "passive"))
      (node (ref "T64") (pin "E") (pinfunction "E_E") (pintype "passive"))
      (node (ref "T65") (pin "E") (pinfunction "E_E") (pintype "passive"))
      (node (ref "T66") (pin "E") (pinfunction "E_E") (pintype "passive"))
      (node (ref "T67") (pin "E") (pinfunction "E_E") (pintype "passive"))
      (node (ref "T68") (pin "E") (pinfunction "E_E") (pintype "passive"))
      (node (ref "T69") (pin "E") (pinfunction "E_E") (pintype "passive"))
      (node (ref "T7") (pin "E") (pinfunction "E_E") (pintype "passive"))
      (node (ref "T70") (pin "E") (pinfunction "E_E") (pintype "passive"))
      (node (ref "T71") (pin "E") (pinfunction "E_E") (pintype "passive"))
      (node (ref "T72") (pin "E") (pinfunction "E_E") (pintype "passive"))
      (node (ref "T8") (pin "E") (pinfunction "E_E") (pintype "passive"))
      (node (ref "T9") (pin "E") (pinfunction "E_E") (pintype "passive"))
    )
    (net (code "2") (name "Net-(IC1A-QA)") (class "Default")
      (node (ref "IC1") (pin "15") (pinfunction "QA_15") (pintype "tri_state"))
      (node (ref "R5") (pin "1") (pinfunction "1_1") (pintype "passive"))
    )
    (net (code "3") (name "Net-(IC1A-QB)") (class "Default")
      (node (ref "IC1") (pin "1") (pinfunction "QB_1") (pintype "tri_state"))
      (node (ref "R6") (pin "1") (pinfunction "1_1") (pintype "passive"))
    )
    (net (code "4") (name "Net-(IC1A-QC)") (class "Default")
      (node (ref "IC1") (pin "2") (pinfunction "QC_2") (pintype "tri_state"))
      (node (ref "R7") (pin "1") (pinfunction "1_1") (pintype "passive"))
    )
    (net (code "5") (name "Net-(IC1A-QD)") (class "Default")
      (node (ref "IC1") (pin "3") (pinfunction "QD_3") (pintype "tri_state"))
      (node (ref "R8") (pin "1") (pinfunction "1_1") (pintype "passive"))
    )
    (net (code "6") (name "Net-(IC1A-QE)") (class "Default")
      (node (ref "IC1") (pin "4") (pinfunction "QE_4") (pintype "tri_state"))
      (node (ref "R9") (pin "1") (pinfunction "1_1") (pintype "passive"))
    )
    (net (code "7") (name "Net-(IC1A-QF)") (class "Default")
      (node (ref "IC1") (pin "5") (pinfunction "QF_5") (pintype "tri_state"))
      (node (ref "R10") (pin "1") (pinfunction "1_1") (pintype "passive"))
    )
    (net (code "8") (name "Net-(IC1A-QG)") (class "Default")
      (node (ref "IC1") (pin "6") (pinfunction "QG_6") (pintype "tri_state"))
      (node (ref "R11") (pin "1") (pinfunction "1_1") (pintype "passive"))
    )
    (net (code "9") (name "Net-(IC1A-QH)") (class "Default")
      (node (ref "IC1") (pin "7") (pinfunction "QH_7") (pintype "tri_state"))
      (node (ref "R12") (pin "1") (pinfunction "1_1") (pintype "passive"))
    )
    (net (code "10") (name "Net-(IC1A-QH*)") (class "Default")
      (node (ref "IC1") (pin "9") (pinfunction "QH*_9") (pintype "tri_state"))
      (node (ref "IC2") (pin "14") (pinfunction "SER_14") (pintype "input"))
    )
    (net (code "11") (name "Net-(IC1A-RCK)") (class "Default")
      (node (ref "IC1") (pin "12") (pinfunction "RCK_12") (pintype "input"))
      (node (ref "IC2") (pin "12") (pinfunction "RCK_12") (pintype "input"))
      (node (ref "IC3") (pin "12") (pinfunction "RCK_12") (pintype "input"))
      (node (ref "IC4") (pin "12") (pinfunction "RCK_12") (pintype "input"))
      (node (ref "IC5") (pin "12") (pinfunction "RCK_12") (pintype "input"))
      (node (ref "IC6") (pin "12") (pinfunction "RCK_12") (pintype "input"))
      (node (ref "IC7") (pin "12") (pinfunction "RCK_12") (pintype "input"))
      (node (ref "IC8") (pin "12") (pinfunction "RCK_12") (pintype "input"))
      (node (ref "IC9") (pin "12") (pinfunction "RCK_12") (pintype "input"))
      (node (ref "J1") (pin "2") (pinfunction "S_2") (pintype "passive"))
    )
    (net (code "12") (name "Net-(IC1A-SCK)") (class "Default")
      (node (ref "IC1") (pin "11") (pinfunction "SCK_11") (pintype "input"))
      (node (ref "IC2") (pin "11") (pinfunction "SCK_11") (pintype "input"))
      (node (ref "IC3") (pin "11") (pinfunction "SCK_11") (pintype "input"))
      (node (ref "IC4") (pin "11") (pinfunction "SCK_11") (pintype "input"))
      (node (ref "IC5") (pin "11") (pinfunction "SCK_11") (pintype "input"))
      (node (ref "IC6") (pin "11") (pinfunction "SCK_11") (pintype "input"))
      (node (ref "IC7") (pin "11") (pinfunction "SCK_11") (pintype "input"))
      (node (ref "IC8") (pin "11") (pinfunction "SCK_11") (pintype "input"))
      (node (ref "IC9") (pin "11") (pinfunction "SCK_11") (pintype "input"))
      (node (ref "J1") (pin "1") (pinfunction "S_1") (pintype "passive"))
    )
    (net (code "13") (name "Net-(IC1A-SER)") (class "Default")
      (node (ref "IC1") (pin "14") (pinfunction "SER_14") (pintype "input"))
      (node (ref "J1") (pin "3") (pinfunction "S_3") (pintype "passive"))
    )
    (net (code "14") (name "Net-(IC2A-QA)") (class "Default")
      (node (ref "IC2") (pin "15") (pinfunction "QA_15") (pintype "tri_state"))
      (node (ref "R22") (pin "1") (pinfunction "1_1") (pintype "passive"))
    )
    (net (code "15") (name "Net-(IC2A-QB)") (class "Default")
      (node (ref "IC2") (pin "1") (pinfunction "QB_1") (pintype "tri_state"))
      (node (ref "R23") (pin "1") (pinfunction "1_1") (pintype "passive"))
    )
    (net (code "16") (name "Net-(IC2A-QC)") (class "Default")
      (node (ref "IC2") (pin "2") (pinfunction "QC_2") (pintype "tri_state"))
      (node (ref "R24") (pin "1") (pinfunction "1_1") (pintype "passive"))
    )
    (net (code "17") (name "Net-(IC2A-QD)") (class "Default")
      (node (ref "IC2") (pin "3") (pinfunction "QD_3") (pintype "tri_state"))
      (node (ref "R25") (pin "1") (pinfunction "1_1") (pintype "passive"))
    )
    (net (code "18") (name "Net-(IC2A-QE)") (class "Default")
      (node (ref "IC2") (pin "4") (pinfunction "QE_4") (pintype "tri_state"))
      (node (ref "R1") (pin "1") (pinfunction "1_1") (pintype "passive"))
    )
    (net (code "19") (name "Net-(IC2A-QF)") (class "Default")
      (node (ref "IC2") (pin "5") (pinfunction "QF_5") (pintype "tri_state"))
      (node (ref "R2") (pin "1") (pinfunction "1_1") (pintype "passive"))
    )
    (net (code "20") (name "Net-(IC2A-QG)") (class "Default")
      (node (ref "IC2") (pin "6") (pinfunction "QG_6") (pintype "tri_state"))
      (node (ref "R3") (pin "1") (pinfunction "1_1") (pintype "passive"))
    )
    (net (code "21") (name "Net-(IC2A-QH)") (class "Default")
      (node (ref "IC2") (pin "7") (pinfunction "QH_7") (pintype "tri_state"))
      (node (ref "R4") (pin "1") (pinfunction "1_1") (pintype "passive"))
    )
    (net (code "22") (name "Net-(IC2A-QH*)") (class "Default")
      (node (ref "IC2") (pin "9") (pinfunction "QH*_9") (pintype "tri_state"))
      (node (ref "IC3") (pin "14") (pinfunction "SER_14") (pintype "input"))
    )
    (net (code "23") (name "Net-(IC3A-QA)") (class "Default")
      (node (ref "IC3") (pin "15") (pinfunction "QA_15") (pintype "tri_state"))
      (node (ref "R14") (pin "1") (pinfunction "1_1") (pintype "passive"))
    )
    (net (code "24") (name "Net-(IC3A-QB)") (class "Default")
      (node (ref "IC3") (pin "1") (pinfunction "QB_1") (pintype "tri_state"))
      (node (ref "R15") (pin "1") (pinfunction "1_1") (pintype "passive"))
    )
    (net (code "25") (name "Net-(IC3A-QC)") (class "Default")
      (node (ref "IC3") (pin "2") (pinfunction "QC_2") (pintype "tri_state"))
      (node (ref "R16") (pin "1") (pinfunction "1_1") (pintype "passive"))
    )
    (net (code "26") (name "Net-(IC3A-QD)") (class "Default")
      (node (ref "IC3") (pin "3") (pinfunction "QD_3") (pintype "tri_state"))
      (node (ref "R17") (pin "1") (pinfunction "1_1") (pintype "passive"))
    )
    (net (code "27") (name "Net-(IC3A-QE)") (class "Default")
      (node (ref "IC3") (pin "4") (pinfunction "QE_4") (pintype "tri_state"))
      (node (ref "R18") (pin "1") (pinfunction "1_1") (pintype "passive"))
    )
    (net (code "28") (name "Net-(IC3A-QF)") (class "Default")
      (node (ref "IC3") (pin "5") (pinfunction "QF_5") (pintype "tri_state"))
      (node (ref "R19") (pin "1") (pinfunction "1_1") (pintype "passive"))
    )
    (net (code "29") (name "Net-(IC3A-QG)") (class "Default")
      (node (ref "IC3") (pin "6") (pinfunction "QG_6") (pintype "tri_state"))
      (node (ref "R20") (pin "1") (pinfunction "1_1") (pintype "passive"))
    )
    (net (code "30") (name "Net-(IC3A-QH)") (class "Default")
      (node (ref "IC3") (pin "7") (pinfunction "QH_7") (pintype "tri_state"))
      (node (ref "R21") (pin "1") (pinfunction "1_1") (pintype "passive"))
    )
    (net (code "31") (name "Net-(IC3A-QH*)") (class "Default")
      (node (ref "IC3") (pin "9") (pinfunction "QH*_9") (pintype "tri_state"))
      (node (ref "IC4") (pin "14") (pinfunction "SER_14") (pintype "input"))
    )
    (net (code "32") (name "Net-(IC4A-QA)") (class "Default")
      (node (ref "IC4") (pin "15") (pinfunction "QA_15") (pintype "tri_state"))
      (node (ref "R31") (pin "1") (pinfunction "1_1") (pintype "passive"))
    )
    (net (code "33") (name "Net-(IC4A-QB)") (class "Default")
      (node (ref "IC4") (pin "1") (pinfunction "QB_1") (pintype "tri_state"))
      (node (ref "R32") (pin "1") (pinfunction "1_1") (pintype "passive"))
    )
    (net (code "34") (name "Net-(IC4A-QC)") (class "Default")
      (node (ref "IC4") (pin "2") (pinfunction "QC_2") (pintype "tri_state"))
      (node (ref "R33") (pin "1") (pinfunction "1_1") (pintype "passive"))
    )
    (net (code "35") (name "Net-(IC4A-QD)") (class "Default")
      (node (ref "IC4") (pin "3") (pinfunction "QD_3") (pintype "tri_state"))
      (node (ref "R34") (pin "1") (pinfunction "1_1") (pintype "passive"))
    )
    (net (code "36") (name "Net-(IC4A-QE)") (class "Default")
      (node (ref "IC4") (pin "4") (pinfunction "QE_4") (pintype "tri_state"))
      (node (ref "R35") (pin "1") (pinfunction "1_1") (pintype "passive"))
    )
    (net (code "37") (name "Net-(IC4A-QF)") (class "Default")
      (node (ref "IC4") (pin "5") (pinfunction "QF_5") (pintype "tri_state"))
      (node (ref "R36") (pin "1") (pinfunction "1_1") (pintype "passive"))
    )
    (net (code "38") (name "Net-(IC4A-QG)") (class "Default")
      (node (ref "IC4") (pin "6") (pinfunction "QG_6") (pintype "tri_state"))
      (node (ref "R37") (pin "1") (pinfunction "1_1") (pintype "passive"))
    )
    (net (code "39") (name "Net-(IC4A-QH)") (class "Default")
      (node (ref "IC4") (pin "7") (pinfunction "QH_7") (pintype "tri_state"))
      (node (ref "R38") (pin "1") (pinfunction "1_1") (pintype "passive"))
    )
    (net (code "40") (name "Net-(IC4A-QH*)") (class "Default")
      (node (ref "IC4") (pin "9") (pinfunction "QH*_9") (pintype "tri_state"))
      (node (ref "IC5") (pin "14") (pinfunction "SER_14") (pintype "input"))
    )
    (net (code "41") (name "Net-(IC5A-QA)") (class "Default")
      (node (ref "IC5") (pin "15") (pinfunction "QA_15") (pintype "tri_state"))
      (node (ref "R48") (pin "1") (pinfunction "1_1") (pintype "passive"))
    )
    (net (code "42") (name "Net-(IC5A-QB)") (class "Default")
      (node (ref "IC5") (pin "1") (pinfunction "QB_1") (pintype "tri_state"))
      (node (ref "R49") (pin "1") (pinfunction "1_1") (pintype "passive"))
    )
    (net (code "43") (name "Net-(IC5A-QC)") (class "Default")
      (node (ref "IC5") (pin "2") (pinfunction "QC_2") (pintype "tri_state"))
      (node (ref "R50") (pin "1") (pinfunction "1_1") (pintype "passive"))
    )
    (net (code "44") (name "Net-(IC5A-QD)") (class "Default")
      (node (ref "IC5") (pin "3") (pinfunction "QD_3") (pintype "tri_state"))
      (node (ref "R51") (pin "1") (pinfunction "1_1") (pintype "passive"))
    )
    (net (code "45") (name "Net-(IC5A-QE)") (class "Default")
      (node (ref "IC5") (pin "4") (pinfunction "QE_4") (pintype "tri_state"))
      (node (ref "R27") (pin "1") (pinfunction "1_1") (pintype "passive"))
    )
    (net (code "46") (name "Net-(IC5A-QF)") (class "Default")
      (node (ref "IC5") (pin "5") (pinfunction "QF_5") (pintype "tri_state"))
      (node (ref "R28") (pin "1") (pinfunction "1_1") (pintype "passive"))
    )
    (net (code "47") (name "Net-(IC5A-QG)") (class "Default")
      (node (ref "IC5") (pin "6") (pinfunction "QG_6") (pintype "tri_state"))
      (node (ref "R29") (pin "1") (pinfunction "1_1") (pintype "passive"))
    )
    (net (code "48") (name "Net-(IC5A-QH)") (class "Default")
      (node (ref "IC5") (pin "7") (pinfunction "QH_7") (pintype "tri_state"))
      (node (ref "R30") (pin "1") (pinfunction "1_1") (pintype "passive"))
    )
    (net (code "49") (name "Net-(IC5A-QH*)") (class "Default")
      (node (ref "IC5") (pin "9") (pinfunction "QH*_9") (pintype "tri_state"))
      (node (ref "IC6") (pin "14") (pinfunction "SER_14") (pintype "input"))
    )
    (net (code "50") (name "Net-(IC6A-QA)") (class "Default")
      (node (ref "IC6") (pin "15") (pinfunction "QA_15") (pintype "tri_state"))
      (node (ref "R40") (pin "1") (pinfunction "1_1") (pintype "passive"))
    )
    (net (code "51") (name "Net-(IC6A-QB)") (class "Default")
      (node (ref "IC6") (pin "1") (pinfunction "QB_1") (pintype "tri_state"))
      (node (ref "R41") (pin "1") (pinfunction "1_1") (pintype "passive"))
    )
    (net (code "52") (name "Net-(IC6A-QC)") (class "Default")
      (node (ref "IC6") (pin "2") (pinfunction "QC_2") (pintype "tri_state"))
      (node (ref "R42") (pin "1") (pinfunction "1_1") (pintype "passive"))
    )
    (net (code "53") (name "Net-(IC6A-QD)") (class "Default")
      (node (ref "IC6") (pin "3") (pinfunction "QD_3") (pintype "tri_state"))
      (node (ref "R43") (pin "1") (pinfunction "1_1") (pintype "passive"))
    )
    (net (code "54") (name "Net-(IC6A-QE)") (class "Default")
      (node (ref "IC6") (pin "4") (pinfunction "QE_4") (pintype "tri_state"))
      (node (ref "R44") (pin "1") (pinfunction "1_1") (pintype "passive"))
    )
    (net (code "55") (name "Net-(IC6A-QF)") (class "Default")
      (node (ref "IC6") (pin "5") (pinfunction "QF_5") (pintype "tri_state"))
      (node (ref "R45") (pin "1") (pinfunction "1_1") (pintype "passive"))
    )
    (net (code "56") (name "Net-(IC6A-QG)") (class "Default")
      (node (ref "IC6") (pin "6") (pinfunction "QG_6") (pintype "tri_state"))
      (node (ref "R46") (pin "1") (pinfunction "1_1") (pintype "passive"))
    )
    (net (code "57") (name "Net-(IC6A-QH)") (class "Default")
      (node (ref "IC6") (pin "7") (pinfunction "QH_7") (pintype "tri_state"))
      (node (ref "R47") (pin "1") (pinfunction "1_1") (pintype "passive"))
    )
    (net (code "58") (name "Net-(IC6A-QH*)") (class "Default")
      (node (ref "IC6") (pin "9") (pinfunction "QH*_9") (pintype "tri_state"))
      (node (ref "IC7") (pin "14") (pinfunction "SER_14") (pintype "input"))
    )
    (net (code "59") (name "Net-(IC7A-QA)") (class "Default")
      (node (ref "IC7") (pin "15") (pinfunction "QA_15") (pintype "tri_state"))
      (node (ref "R57") (pin "1") (pinfunction "1_1") (pintype "passive"))
    )
    (net (code "60") (name "Net-(IC7A-QB)") (class "Default")
      (node (ref "IC7") (pin "1") (pinfunction "QB_1") (pintype "tri_state"))
      (node (ref "R58") (pin "1") (pinfunction "1_1") (pintype "passive"))
    )
    (net (code "61") (name "Net-(IC7A-QC)") (class "Default")
      (node (ref "IC7") (pin "2") (pinfunction "QC_2") (pintype "tri_state"))
      (node (ref "R59") (pin "1") (pinfunction "1_1") (pintype "passive"))
    )
    (net (code "62") (name "Net-(IC7A-QD)") (class "Default")
      (node (ref "IC7") (pin "3") (pinfunction "QD_3") (pintype "tri_state"))
      (node (ref "R60") (pin "1") (pinfunction "1_1") (pintype "passive"))
    )
    (net (code "63") (name "Net-(IC7A-QE)") (class "Default")
      (node (ref "IC7") (pin "4") (pinfunction "QE_4") (pintype "tri_state"))
      (node (ref "R61") (pin "1") (pinfunction "1_1") (pintype "passive"))
    )
    (net (code "64") (name "Net-(IC7A-QF)") (class "Default")
      (node (ref "IC7") (pin "5") (pinfunction "QF_5") (pintype "tri_state"))
      (node (ref "R62") (pin "1") (pinfunction "1_1") (pintype "passive"))
    )
    (net (code "65") (name "Net-(IC7A-QG)") (class "Default")
      (node (ref "IC7") (pin "6") (pinfunction "QG_6") (pintype "tri_state"))
      (node (ref "R63") (pin "1") (pinfunction "1_1") (pintype "passive"))
    )
    (net (code "66") (name "Net-(IC7A-QH)") (class "Default")
      (node (ref "IC7") (pin "7") (pinfunction "QH_7") (pintype "tri_state"))
      (node (ref "R64") (pin "1") (pinfunction "1_1") (pintype "passive"))
    )
    (net (code "67") (name "Net-(IC7A-QH*)") (class "Default")
      (node (ref "IC7") (pin "9") (pinfunction "QH*_9") (pintype "tri_state"))
      (node (ref "IC8") (pin "14") (pinfunction "SER_14") (pintype "input"))
    )
    (net (code "68") (name "Net-(IC8A-QA)") (class "Default")
      (node (ref "IC8") (pin "15") (pinfunction "QA_15") (pintype "tri_state"))
      (node (ref "R74") (pin "1") (pinfunction "1_1") (pintype "passive"))
    )
    (net (code "69") (name "Net-(IC8A-QB)") (class "Default")
      (node (ref "IC8") (pin "1") (pinfunction "QB_1") (pintype "tri_state"))
      (node (ref "R75") (pin "1") (pinfunction "1_1") (pintype "passive"))
    )
    (net (code "70") (name "Net-(IC8A-QC)") (class "Default")
      (node (ref "IC8") (pin "2") (pinfunction "QC_2") (pintype "tri_state"))
      (node (ref "R76") (pin "1") (pinfunction "1_1") (pintype "passive"))
    )
    (net (code "71") (name "Net-(IC8A-QD)") (class "Default")
      (node (ref "IC8") (pin "3") (pinfunction "QD_3") (pintype "tri_state"))
      (node (ref "R77") (pin "1") (pinfunction "1_1") (pintype "passive"))
    )
    (net (code "72") (name "Net-(IC8A-QE)") (class "Default")
      (node (ref "IC8") (pin "4") (pinfunction "QE_4") (pintype "tri_state"))
      (node (ref "R53") (pin "1") (pinfunction "1_1") (pintype "passive"))
    )
    (net (code "73") (name "Net-(IC8A-QF)") (class "Default")
      (node (ref "IC8") (pin "5") (pinfunction "QF_5") (pintype "tri_state"))
      (node (ref "R54") (pin "1") (pinfunction "1_1") (pintype "passive"))
    )
    (net (code "74") (name "Net-(IC8A-QG)") (class "Default")
      (node (ref "IC8") (pin "6") (pinfunction "QG_6") (pintype "tri_state"))
      (node (ref "R55") (pin "1") (pinfunction "1_1") (pintype "passive"))
    )
    (net (code "75") (name "Net-(IC8A-QH)") (class "Default")
      (node (ref "IC8") (pin "7") (pinfunction "QH_7") (pintype "tri_state"))
      (node (ref "R56") (pin "1") (pinfunction "1_1") (pintype "passive"))
    )
    (net (code "76") (name "Net-(IC8A-QH*)") (class "Default")
      (node (ref "IC8") (pin "9") (pinfunction "QH*_9") (pintype "tri_state"))
      (node (ref "IC9") (pin "14") (pinfunction "SER_14") (pintype "input"))
    )
    (net (code "77") (name "Net-(IC9A-QA)") (class "Default")
      (node (ref "IC9") (pin "15") (pinfunction "QA_15") (pintype "tri_state"))
      (node (ref "R66") (pin "1") (pinfunction "1_1") (pintype "passive"))
    )
    (net (code "78") (name "Net-(IC9A-QB)") (class "Default")
      (node (ref "IC9") (pin "1") (pinfunction "QB_1") (pintype "tri_state"))
      (node (ref "R67") (pin "1") (pinfunction "1_1") (pintype "passive"))
    )
    (net (code "79") (name "Net-(IC9A-QC)") (class "Default")
      (node (ref "IC9") (pin "2") (pinfunction "QC_2") (pintype "tri_state"))
      (node (ref "R68") (pin "1") (pinfunction "1_1") (pintype "passive"))
    )
    (net (code "80") (name "Net-(IC9A-QD)") (class "Default")
      (node (ref "IC9") (pin "3") (pinfunction "QD_3") (pintype "tri_state"))
      (node (ref "R69") (pin "1") (pinfunction "1_1") (pintype "passive"))
    )
    (net (code "81") (name "Net-(IC9A-QE)") (class "Default")
      (node (ref "IC9") (pin "4") (pinfunction "QE_4") (pintype "tri_state"))
      (node (ref "R70") (pin "1") (pinfunction "1_1") (pintype "passive"))
    )
    (net (code "82") (name "Net-(IC9A-QF)") (class "Default")
      (node (ref "IC9") (pin "5") (pinfunction "QF_5") (pintype "tri_state"))
      (node (ref "R71") (pin "1") (pinfunction "1_1") (pintype "passive"))
    )
    (net (code "83") (name "Net-(IC9A-QG)") (class "Default")
      (node (ref "IC9") (pin "6") (pinfunction "QG_6") (pintype "tri_state"))
      (node (ref "R72") (pin "1") (pinfunction "1_1") (pintype "passive"))
    )
    (net (code "84") (name "Net-(IC9A-QH)") (class "Default")
      (node (ref "IC9") (pin "7") (pinfunction "QH_7") (pintype "tri_state"))
      (node (ref "R73") (pin "1") (pinfunction "1_1") (pintype "passive"))
    )
    (net (code "85") (name "Net-(J2A-S)") (class "Default")
      (node (ref "J2") (pin "1") (pinfunction "S_1") (pintype "passive"))
      (node (ref "R13") (pin "2") (pinfunction "2_2") (pintype "passive"))
      (node (ref "R26") (pin "2") (pinfunction "2_2") (pintype "passive"))
      (node (ref "R39") (pin "2") (pinfunction "2_2") (pintype "passive"))
      (node (ref "R52") (pin "2") (pinfunction "2_2") (pintype "passive"))
      (node (ref "R65") (pin "2") (pinfunction "2_2") (pintype "passive"))
      (node (ref "R78") (pin "2") (pinfunction "2_2") (pintype "passive"))
    )
    (net (code "86") (name "Net-(R1-Pad2)") (class "Default")
      (node (ref "R1") (pin "2") (pinfunction "2_2") (pintype "passive"))
      (node (ref "T1") (pin "B") (pinfunction "B_B") (pintype "passive"))
    )
    (net (code "87") (name "Net-(R2-Pad2)") (class "Default")
      (node (ref "R2") (pin "2") (pinfunction "2_2") (pintype "passive"))
      (node (ref "T2") (pin "B") (pinfunction "B_B") (pintype "passive"))
    )
    (net (code "88") (name "Net-(R3-Pad2)") (class "Default")
      (node (ref "R3") (pin "2") (pinfunction "2_2") (pintype "passive"))
      (node (ref "T3") (pin "B") (pinfunction "B_B") (pintype "passive"))
    )
    (net (code "89") (name "Net-(R4-Pad2)") (class "Default")
      (node (ref "R4") (pin "2") (pinfunction "2_2") (pintype "passive"))
      (node (ref "T4") (pin "B") (pinfunction "B_B") (pintype "passive"))
    )
    (net (code "90") (name "Net-(R5-Pad2)") (class "Default")
      (node (ref "R5") (pin "2") (pinfunction "2_2") (pintype "passive"))
      (node (ref "T5") (pin "B") (pinfunction "B_B") (pintype "passive"))
    )
    (net (code "91") (name "Net-(R6-Pad2)") (class "Default")
      (node (ref "R6") (pin "2") (pinfunction "2_2") (pintype "passive"))
      (node (ref "T6") (pin "B") (pinfunction "B_B") (pintype "passive"))
    )
    (net (code "92") (name "Net-(R7-Pad2)") (class "Default")
      (node (ref "R7") (pin "2") (pinfunction "2_2") (pintype "passive"))
      (node (ref "T7") (pin "B") (pinfunction "B_B") (pintype "passive"))
    )
    (net (code "93") (name "Net-(R8-Pad2)") (class "Default")
      (node (ref "R8") (pin "2") (pinfunction "2_2") (pintype "passive"))
      (node (ref "T8") (pin "B") (pinfunction "B_B") (pintype "passive"))
    )
    (net (code "94") (name "Net-(R9-Pad2)") (class "Default")
      (node (ref "R9") (pin "2") (pinfunction "2_2") (pintype "passive"))
      (node (ref "T9") (pin "B") (pinfunction "B_B") (pintype "passive"))
    )
    (net (code "95") (name "Net-(R10-Pad2)") (class "Default")
      (node (ref "R10") (pin "2") (pinfunction "2_2") (pintype "passive"))
      (node (ref "T10") (pin "B") (pinfunction "B_B") (pintype "passive"))
    )
    (net (code "96") (name "Net-(R11-Pad2)") (class "Default")
      (node (ref "R11") (pin "2") (pinfunction "2_2") (pintype "passive"))
      (node (ref "T11") (pin "B") (pinfunction "B_B") (pintype "passive"))
    )
    (net (code "97") (name "Net-(R12-Pad2)") (class "Default")
      (node (ref "R12") (pin "2") (pinfunction "2_2") (pintype "passive"))
      (node (ref "T12") (pin "B") (pinfunction "B_B") (pintype "passive"))
    )
    (net (code "98") (name "Net-(R13-Pad1)") (class "Default")
      (node (ref "R13") (pin "1") (pinfunction "1_1") (pintype "passive"))
      (node (ref "SV1") (pin "13") (pinfunction "13_13") (pintype "passive"))
    )
    (net (code "99") (name "Net-(R14-Pad2)") (class "Default")
      (node (ref "R14") (pin "2") (pinfunction "2_2") (pintype "passive"))
      (node (ref "T13") (pin "B") (pinfunction "B_B") (pintype "passive"))
    )
    (net (code "100") (name "Net-(R15-Pad2)") (class "Default")
      (node (ref "R15") (pin "2") (pinfunction "2_2") (pintype "passive"))
      (node (ref "T14") (pin "B") (pinfunction "B_B") (pintype "passive"))
    )
    (net (code "101") (name "Net-(R16-Pad2)") (class "Default")
      (node (ref "R16") (pin "2") (pinfunction "2_2") (pintype "passive"))
      (node (ref "T15") (pin "B") (pinfunction "B_B") (pintype "passive"))
    )
    (net (code "102") (name "Net-(R17-Pad2)") (class "Default")
      (node (ref "R17") (pin "2") (pinfunction "2_2") (pintype "passive"))
      (node (ref "T16") (pin "B") (pinfunction "B_B") (pintype "passive"))
    )
    (net (code "103") (name "Net-(R18-Pad2)") (class "Default")
      (node (ref "R18") (pin "2") (pinfunction "2_2") (pintype "passive"))
      (node (ref "T17") (pin "B") (pinfunction "B_B") (pintype "passive"))
    )
    (net (code "104") (name "Net-(R19-Pad2)") (class "Default")
      (node (ref "R19") (pin "2") (pinfunction "2_2") (pintype "passive"))
      (node (ref "T18") (pin "B") (pinfunction "B_B") (pintype "passive"))
    )
    (net (code "105") (name "Net-(R20-Pad2)") (class "Default")
      (node (ref "R20") (pin "2") (pinfunction "2_2") (pintype "passive"))
      (node (ref "T19") (pin "B") (pinfunction "B_B") (pintype "passive"))
    )
    (net (code "106") (name "Net-(R21-Pad2)") (class "Default")
      (node (ref "R21") (pin "2") (pinfunction "2_2") (pintype "passive"))
      (node (ref "T20") (pin "B") (pinfunction "B_B") (pintype "passive"))
    )
    (net (code "107") (name "Net-(R22-Pad2)") (class "Default")
      (node (ref "R22") (pin "2") (pinfunction "2_2") (pintype "passive"))
      (node (ref "T21") (pin "B") (pinfunction "B_B") (pintype "passive"))
    )
    (net (code "108") (name "Net-(R23-Pad2)") (class "Default")
      (node (ref "R23") (pin "2") (pinfunction "2_2") (pintype "passive"))
      (node (ref "T22") (pin "B") (pinfunction "B_B") (pintype "passive"))
    )
    (net (code "109") (name "Net-(R24-Pad2)") (class "Default")
      (node (ref "R24") (pin "2") (pinfunction "2_2") (pintype "passive"))
      (node (ref "T23") (pin "B") (pinfunction "B_B") (pintype "passive"))
    )
    (net (code "110") (name "Net-(R25-Pad2)") (class "Default")
      (node (ref "R25") (pin "2") (pinfunction "2_2") (pintype "passive"))
      (node (ref "T24") (pin "B") (pinfunction "B_B") (pintype "passive"))
    )
    (net (code "111") (name "Net-(R26-Pad1)") (class "Default")
      (node (ref "R26") (pin "1") (pinfunction "1_1") (pintype "passive"))
      (node (ref "SV1") (pin "14") (pinfunction "14_14") (pintype "passive"))
    )
    (net (code "112") (name "Net-(R27-Pad2)") (class "Default")
      (node (ref "R27") (pin "2") (pinfunction "2_2") (pintype "passive"))
      (node (ref "T25") (pin "B") (pinfunction "B_B") (pintype "passive"))
    )
    (net (code "113") (name "Net-(R28-Pad2)") (class "Default")
      (node (ref "R28") (pin "2") (pinfunction "2_2") (pintype "passive"))
      (node (ref "T26") (pin "B") (pinfunction "B_B") (pintype "passive"))
    )
    (net (code "114") (name "Net-(R29-Pad2)") (class "Default")
      (node (ref "R29") (pin "2") (pinfunction "2_2") (pintype "passive"))
      (node (ref "T27") (pin "B") (pinfunction "B_B") (pintype "passive"))
    )
    (net (code "115") (name "Net-(R30-Pad2)") (class "Default")
      (node (ref "R30") (pin "2") (pinfunction "2_2") (pintype "passive"))
      (node (ref "T28") (pin "B") (pinfunction "B_B") (pintype "passive"))
    )
    (net (code "116") (name "Net-(R31-Pad2)") (class "Default")
      (node (ref "R31") (pin "2") (pinfunction "2_2") (pintype "passive"))
      (node (ref "T29") (pin "B") (pinfunction "B_B") (pintype "passive"))
    )
    (net (code "117") (name "Net-(R32-Pad2)") (class "Default")
      (node (ref "R32") (pin "2") (pinfunction "2_2") (pintype "passive"))
      (node (ref "T30") (pin "B") (pinfunction "B_B") (pintype "passive"))
    )
    (net (code "118") (name "Net-(R33-Pad2)") (class "Default")
      (node (ref "R33") (pin "2") (pinfunction "2_2") (pintype "passive"))
      (node (ref "T31") (pin "B") (pinfunction "B_B") (pintype "passive"))
    )
    (net (code "119") (name "Net-(R34-Pad2)") (class "Default")
      (node (ref "R34") (pin "2") (pinfunction "2_2") (pintype "passive"))
      (node (ref "T32") (pin "B") (pinfunction "B_B") (pintype "passive"))
    )
    (net (code "120") (name "Net-(R35-Pad2)") (class "Default")
      (node (ref "R35") (pin "2") (pinfunction "2_2") (pintype "passive"))
      (node (ref "T33") (pin "B") (pinfunction "B_B") (pintype "passive"))
    )
    (net (code "121") (name "Net-(R36-Pad2)") (class "Default")
      (node (ref "R36") (pin "2") (pinfunction "2_2") (pintype "passive"))
      (node (ref "T34") (pin "B") (pinfunction "B_B") (pintype "passive"))
    )
    (net (code "122") (name "Net-(R37-Pad2)") (class "Default")
      (node (ref "R37") (pin "2") (pinfunction "2_2") (pintype "passive"))
      (node (ref "T35") (pin "B") (pinfunction "B_B") (pintype "passive"))
    )
    (net (code "123") (name "Net-(R38-Pad2)") (class "Default")
      (node (ref "R38") (pin "2") (pinfunction "2_2") (pintype "passive"))
      (node (ref "T36") (pin "B") (pinfunction "B_B") (pintype "passive"))
    )
    (net (code "124") (name "Net-(R39-Pad1)") (class "Default")
      (node (ref "R39") (pin "1") (pinfunction "1_1") (pintype "passive"))
      (node (ref "SV2") (pin "13") (pinfunction "13_13") (pintype "passive"))
    )
    (net (code "125") (name "Net-(R40-Pad2)") (class "Default")
      (node (ref "R40") (pin "2") (pinfunction "2_2") (pintype "passive"))
      (node (ref "T37") (pin "B") (pinfunction "B_B") (pintype "passive"))
    )
    (net (code "126") (name "Net-(R41-Pad2)") (class "Default")
      (node (ref "R41") (pin "2") (pinfunction "2_2") (pintype "passive"))
      (node (ref "T38") (pin "B") (pinfunction "B_B") (pintype "passive"))
    )
    (net (code "127") (name "Net-(R42-Pad2)") (class "Default")
      (node (ref "R42") (pin "2") (pinfunction "2_2") (pintype "passive"))
      (node (ref "T39") (pin "B") (pinfunction "B_B") (pintype "passive"))
    )
    (net (code "128") (name "Net-(R43-Pad2)") (class "Default")
      (node (ref "R43") (pin "2") (pinfunction "2_2") (pintype "passive"))
      (node (ref "T40") (pin "B") (pinfunction "B_B") (pintype "passive"))
    )
    (net (code "129") (name "Net-(R44-Pad2)") (class "Default")
      (node (ref "R44") (pin "2") (pinfunction "2_2") (pintype "passive"))
      (node (ref "T41") (pin "B") (pinfunction "B_B") (pintype "passive"))
    )
    (net (code "130") (name "Net-(R45-Pad2)") (class "Default")
      (node (ref "R45") (pin "2") (pinfunction "2_2") (pintype "passive"))
      (node (ref "T42") (pin "B") (pinfunction "B_B") (pintype "passive"))
    )
    (net (code "131") (name "Net-(R46-Pad2)") (class "Default")
      (node (ref "R46") (pin "2") (pinfunction "2_2") (pintype "passive"))
      (node (ref "T43") (pin "B") (pinfunction "B_B") (pintype "passive"))
    )
    (net (code "132") (name "Net-(R47-Pad2)") (class "Default")
      (node (ref "R47") (pin "2") (pinfunction "2_2") (pintype "passive"))
      (node (ref "T44") (pin "B") (pinfunction "B_B") (pintype "passive"))
    )
    (net (code "133") (name "Net-(R48-Pad2)") (class "Default")
      (node (ref "R48") (pin "2") (pinfunction "2_2") (pintype "passive"))
      (node (ref "T45") (pin "B") (pinfunction "B_B") (pintype "passive"))
    )
    (net (code "134") (name "Net-(R49-Pad2)") (class "Default")
      (node (ref "R49") (pin "2") (pinfunction "2_2") (pintype "passive"))
      (node (ref "T46") (pin "B") (pinfunction "B_B") (pintype "passive"))
    )
    (net (code "135") (name "Net-(R50-Pad2)") (class "Default")
      (node (ref "R50") (pin "2") (pinfunction "2_2") (pintype "passive"))
      (node (ref "T47") (pin "B") (pinfunction "B_B") (pintype "passive"))
    )
    (net (code "136") (name "Net-(R51-Pad2)") (class "Default")
      (node (ref "R51") (pin "2") (pinfunction "2_2") (pintype "passive"))
      (node (ref "T48") (pin "B") (pinfunction "B_B") (pintype "passive"))
    )
    (net (code "137") (name "Net-(R52-Pad1)") (class "Default")
      (node (ref "R52") (pin "1") (pinfunction "1_1") (pintype "passive"))
      (node (ref "SV2") (pin "14") (pinfunction "14_14") (pintype "passive"))
    )
    (net (code "138") (name "Net-(R53-Pad2)") (class "Default")
      (node (ref "R53") (pin "2") (pinfunction "2_2") (pintype "passive"))
      (node (ref "T49") (pin "B") (pinfunction "B_B") (pintype "passive"))
    )
    (net (code "139") (name "Net-(R54-Pad2)") (class "Default")
      (node (ref "R54") (pin "2") (pinfunction "2_2") (pintype "passive"))
      (node (ref "T50") (pin "B") (pinfunction "B_B") (pintype "passive"))
    )
    (net (code "140") (name "Net-(R55-Pad2)") (class "Default")
      (node (ref "R55") (pin "2") (pinfunction "2_2") (pintype "passive"))
      (node (ref "T51") (pin "B") (pinfunction "B_B") (pintype "passive"))
    )
    (net (code "141") (name "Net-(R56-Pad2)") (class "Default")
      (node (ref "R56") (pin "2") (pinfunction "2_2") (pintype "passive"))
      (node (ref "T52") (pin "B") (pinfunction "B_B") (pintype "passive"))
    )
    (net (code "142") (name "Net-(R57-Pad2)") (class "Default")
      (node (ref "R57") (pin "2") (pinfunction "2_2") (pintype "passive"))
      (node (ref "T53") (pin "B") (pinfunction "B_B") (pintype "passive"))
    )
    (net (code "143") (name "Net-(R58-Pad2)") (class "Default")
      (node (ref "R58") (pin "2") (pinfunction "2_2") (pintype "passive"))
      (node (ref "T54") (pin "B") (pinfunction "B_B") (pintype "passive"))
    )
    (net (code "144") (name "Net-(R59-Pad2)") (class "Default")
      (node (ref "R59") (pin "2") (pinfunction "2_2") (pintype "passive"))
      (node (ref "T55") (pin "B") (pinfunction "B_B") (pintype "passive"))
    )
    (net (code "145") (name "Net-(R60-Pad2)") (class "Default")
      (node (ref "R60") (pin "2") (pinfunction "2_2") (pintype "passive"))
      (node (ref "T56") (pin "B") (pinfunction "B_B") (pintype "passive"))
    )
    (net (code "146") (name "Net-(R61-Pad2)") (class "Default")
      (node (ref "R61") (pin "2") (pinfunction "2_2") (pintype "passive"))
      (node (ref "T57") (pin "B") (pinfunction "B_B") (pintype "passive"))
    )
    (net (code "147") (name "Net-(R62-Pad2)") (class "Default")
      (node (ref "R62") (pin "2") (pinfunction "2_2") (pintype "passive"))
      (node (ref "T58") (pin "B") (pinfunction "B_B") (pintype "passive"))
    )
    (net (code "148") (name "Net-(R63-Pad2)") (class "Default")
      (node (ref "R63") (pin "2") (pinfunction "2_2") (pintype "passive"))
      (node (ref "T59") (pin "B") (pinfunction "B_B") (pintype "passive"))
    )
    (net (code "149") (name "Net-(R64-Pad2)") (class "Default")
      (node (ref "R64") (pin "2") (pinfunction "2_2") (pintype "passive"))
      (node (ref "T60") (pin "B") (pinfunction "B_B") (pintype "passive"))
    )
    (net (code "150") (name "Net-(R65-Pad1)") (class "Default")
      (node (ref "R65") (pin "1") (pinfunction "1_1") (pintype "passive"))
      (node (ref "SV3") (pin "13") (pinfunction "13_13") (pintype "passive"))
    )
    (net (code "151") (name "Net-(R66-Pad2)") (class "Default")
      (node (ref "R66") (pin "2") (pinfunction "2_2") (pintype "passive"))
      (node (ref "T61") (pin "B") (pinfunction "B_B") (pintype "passive"))
    )
    (net (code "152") (name "Net-(R67-Pad2)") (class "Default")
      (node (ref "R67") (pin "2") (pinfunction "2_2") (pintype "passive"))
      (node (ref "T62") (pin "B") (pinfunction "B_B") (pintype "passive"))
    )
    (net (code "153") (name "Net-(R68-Pad2)") (class "Default")
      (node (ref "R68") (pin "2") (pinfunction "2_2") (pintype "passive"))
      (node (ref "T63") (pin "B") (pinfunction "B_B") (pintype "passive"))
    )
    (net (code "154") (name "Net-(R69-Pad2)") (class "Default")
      (node (ref "R69") (pin "2") (pinfunction "2_2") (pintype "passive"))
      (node (ref "T64") (pin "B") (pinfunction "B_B") (pintype "passive"))
    )
    (net (code "155") (name "Net-(R70-Pad2)") (class "Default")
      (node (ref "R70") (pin "2") (pinfunction "2_2") (pintype "passive"))
      (node (ref "T65") (pin "B") (pinfunction "B_B") (pintype "passive"))
    )
    (net (code "156") (name "Net-(R71-Pad2)") (class "Default")
      (node (ref "R71") (pin "2") (pinfunction "2_2") (pintype "passive"))
      (node (ref "T66") (pin "B") (pinfunction "B_B") (pintype "passive"))
    )
    (net (code "157") (name "Net-(R72-Pad2)") (class "Default")
      (node (ref "R72") (pin "2") (pinfunction "2_2") (pintype "passive"))
      (node (ref "T67") (pin "B") (pinfunction "B_B") (pintype "passive"))
    )
    (net (code "158") (name "Net-(R73-Pad2)") (class "Default")
      (node (ref "R73") (pin "2") (pinfunction "2_2") (pintype "passive"))
      (node (ref "T68") (pin "B") (pinfunction "B_B") (pintype "passive"))
    )
    (net (code "159") (name "Net-(R74-Pad2)") (class "Default")
      (node (ref "R74") (pin "2") (pinfunction "2_2") (pintype "passive"))
      (node (ref "T69") (pin "B") (pinfunction "B_B") (pintype "passive"))
    )
    (net (code "160") (name "Net-(R75-Pad2)") (class "Default")
      (node (ref "R75") (pin "2") (pinfunction "2_2") (pintype "passive"))
      (node (ref "T70") (pin "B") (pinfunction "B_B") (pintype "passive"))
    )
    (net (code "161") (name "Net-(R76-Pad2)") (class "Default")
      (node (ref "R76") (pin "2") (pinfunction "2_2") (pintype "passive"))
      (node (ref "T71") (pin "B") (pinfunction "B_B") (pintype "passive"))
    )
    (net (code "162") (name "Net-(R77-Pad2)") (class "Default")
      (node (ref "R77") (pin "2") (pinfunction "2_2") (pintype "passive"))
      (node (ref "T72") (pin "B") (pinfunction "B_B") (pintype "passive"))
    )
    (net (code "163") (name "Net-(R78-Pad1)") (class "Default")
      (node (ref "R78") (pin "1") (pinfunction "1_1") (pintype "passive"))
      (node (ref "SV3") (pin "14") (pinfunction "14_14") (pintype "passive"))
    )
    (net (code "164") (name "Net-(SV1-Pad1)") (class "Default")
      (node (ref "SV1") (pin "1") (pinfunction "1_1") (pintype "passive"))
      (node (ref "T11") (pin "C") (pinfunction "C_C") (pintype "passive"))
    )
    (net (code "165") (name "Net-(SV1-Pad2)") (class "Default")
      (node (ref "SV1") (pin "2") (pinfunction "2_2") (pintype "passive"))
      (node (ref "T12") (pin "C") (pinfunction "C_C") (pintype "passive"))
    )
    (net (code "166") (name "Net-(SV1-Pad3)") (class "Default")
      (node (ref "SV1") (pin "3") (pinfunction "3_3") (pintype "passive"))
      (node (ref "T9") (pin "C") (pinfunction "C_C") (pintype "passive"))
    )
    (net (code "167") (name "Net-(SV1-Pad4)") (class "Default")
      (node (ref "SV1") (pin "4") (pinfunction "4_4") (pintype "passive"))
      (node (ref "T10") (pin "C") (pinfunction "C_C") (pintype "passive"))
    )
    (net (code "168") (name "Net-(SV1-Pad5)") (class "Default")
      (node (ref "SV1") (pin "5") (pinfunction "5_5") (pintype "passive"))
      (node (ref "T7") (pin "C") (pinfunction "C_C") (pintype "passive"))
    )
    (net (code "169") (name "Net-(SV1-Pad6)") (class "Default")
      (node (ref "SV1") (pin "6") (pinfunction "6_6") (pintype "passive"))
      (node (ref "T8") (pin "C") (pinfunction "C_C") (pintype "passive"))
    )
    (net (code "170") (name "Net-(SV1-Pad7)") (class "Default")
      (node (ref "SV1") (pin "7") (pinfunction "7_7") (pintype "passive"))
      (node (ref "T5") (pin "C") (pinfunction "C_C") (pintype "passive"))
    )
    (net (code "171") (name "Net-(SV1-Pad8)") (class "Default")
      (node (ref "SV1") (pin "8") (pinfunction "8_8") (pintype "passive"))
      (node (ref "T6") (pin "C") (pinfunction "C_C") (pintype "passive"))
    )
    (net (code "172") (name "Net-(SV1-Pad9)") (class "Default")
      (node (ref "SV1") (pin "9") (pinfunction "9_9") (pintype "passive"))
      (node (ref "T3") (pin "C") (pinfunction "C_C") (pintype "passive"))
    )
    (net (code "173") (name "Net-(SV1-Pad10)") (class "Default")
      (node (ref "SV1") (pin "10") (pinfunction "10_10") (pintype "passive"))
      (node (ref "T4") (pin "C") (pinfunction "C_C") (pintype "passive"))
    )
    (net (code "174") (name "Net-(SV1-Pad11)") (class "Default")
      (node (ref "SV1") (pin "11") (pinfunction "11_11") (pintype "passive"))
      (node (ref "T1") (pin "C") (pinfunction "C_C") (pintype "passive"))
    )
    (net (code "175") (name "Net-(SV1-Pad12)") (class "Default")
      (node (ref "SV1") (pin "12") (pinfunction "12_12") (pintype "passive"))
      (node (ref "T2") (pin "C") (pinfunction "C_C") (pintype "passive"))
    )
    (net (code "176") (name "Net-(SV1-Pad15)") (class "Default")
      (node (ref "SV1") (pin "15") (pinfunction "15_15") (pintype "passive"))
      (node (ref "T23") (pin "C") (pinfunction "C_C") (pintype "passive"))
    )
    (net (code "177") (name "Net-(SV1-Pad16)") (class "Default")
      (node (ref "SV1") (pin "16") (pinfunction "16_16") (pintype "passive"))
      (node (ref "T24") (pin "C") (pinfunction "C_C") (pintype "passive"))
    )
    (net (code "178") (name "Net-(SV1-Pad17)") (class "Default")
      (node (ref "SV1") (pin "17") (pinfunction "17_17") (pintype "passive"))
      (node (ref "T21") (pin "C") (pinfunction "C_C") (pintype "passive"))
    )
    (net (code "179") (name "Net-(SV1-Pad18)") (class "Default")
      (node (ref "SV1") (pin "18") (pinfunction "18_18") (pintype "passive"))
      (node (ref "T22") (pin "C") (pinfunction "C_C") (pintype "passive"))
    )
    (net (code "180") (name "Net-(SV1-Pad19)") (class "Default")
      (node (ref "SV1") (pin "19") (pinfunction "19_19") (pintype "passive"))
      (node (ref "T19") (pin "C") (pinfunction "C_C") (pintype "passive"))
    )
    (net (code "181") (name "Net-(SV1-Pad20)") (class "Default")
      (node (ref "SV1") (pin "20") (pinfunction "20_20") (pintype "passive"))
      (node (ref "T20") (pin "C") (pinfunction "C_C") (pintype "passive"))
    )
    (net (code "182") (name "Net-(SV1-Pad21)") (class "Default")
      (node (ref "SV1") (pin "21") (pinfunction "21_21") (pintype "passive"))
      (node (ref "T17") (pin "C") (pinfunction "C_C") (pintype "passive"))
    )
    (net (code "183") (name "Net-(SV1-Pad22)") (class "Default")
      (node (ref "SV1") (pin "22") (pinfunction "22_22") (pintype "passive"))
      (node (ref "T18") (pin "C") (pinfunction "C_C") (pintype "passive"))
    )
    (net (code "184") (name "Net-(SV1-Pad23)") (class "Default")
      (node (ref "SV1") (pin "23") (pinfunction "23_23") (pintype "passive"))
      (node (ref "T15") (pin "C") (pinfunction "C_C") (pintype "passive"))
    )
    (net (code "185") (name "Net-(SV1-Pad24)") (class "Default")
      (node (ref "SV1") (pin "24") (pinfunction "24_24") (pintype "passive"))
      (node (ref "T16") (pin "C") (pinfunction "C_C") (pintype "passive"))
    )
    (net (code "186") (name "Net-(SV1-Pad25)") (class "Default")
      (node (ref "SV1") (pin "25") (pinfunction "25_25") (pintype "passive"))
      (node (ref "T14") (pin "C") (pinfunction "C_C") (pintype "passive"))
    )
    (net (code "187") (name "Net-(SV1-Pad26)") (class "Default")
      (node (ref "SV1") (pin "26") (pinfunction "26_26") (pintype "passive"))
      (node (ref "T13") (pin "C") (pinfunction "C_C") (pintype "passive"))
    )
    (net (code "188") (name "Net-(SV2-Pad1)") (class "Default")
      (node (ref "SV2") (pin "1") (pinfunction "1_1") (pintype "passive"))
      (node (ref "T35") (pin "C") (pinfunction "C_C") (pintype "passive"))
    )
    (net (code "189") (name "Net-(SV2-Pad2)") (class "Default")
      (node (ref "SV2") (pin "2") (pinfunction "2_2") (pintype "passive"))
      (node (ref "T36") (pin "C") (pinfunction "C_C") (pintype "passive"))
    )
    (net (code "190") (name "Net-(SV2-Pad3)") (class "Default")
      (node (ref "SV2") (pin "3") (pinfunction "3_3") (pintype "passive"))
      (node (ref "T33") (pin "C") (pinfunction "C_C") (pintype "passive"))
    )
    (net (code "191") (name "Net-(SV2-Pad4)") (class "Default")
      (node (ref "SV2") (pin "4") (pinfunction "4_4") (pintype "passive"))
      (node (ref "T34") (pin "C") (pinfunction "C_C") (pintype "passive"))
    )
    (net (code "192") (name "Net-(SV2-Pad5)") (class "Default")
      (node (ref "SV2") (pin "5") (pinfunction "5_5") (pintype "passive"))
      (node (ref "T31") (pin "C") (pinfunction "C_C") (pintype "passive"))
    )
    (net (code "193") (name "Net-(SV2-Pad6)") (class "Default")
      (node (ref "SV2") (pin "6") (pinfunction "6_6") (pintype "passive"))
      (node (ref "T32") (pin "C") (pinfunction "C_C") (pintype "passive"))
    )
    (net (code "194") (name "Net-(SV2-Pad7)") (class "Default")
      (node (ref "SV2") (pin "7") (pinfunction "7_7") (pintype "passive"))
      (node (ref "T29") (pin "C") (pinfunction "C_C") (pintype "passive"))
    )
    (net (code "195") (name "Net-(SV2-Pad8)") (class "Default")
      (node (ref "SV2") (pin "8") (pinfunction "8_8") (pintype "passive"))
      (node (ref "T30") (pin "C") (pinfunction "C_C") (pintype "passive"))
    )
    (net (code "196") (name "Net-(SV2-Pad9)") (class "Default")
      (node (ref "SV2") (pin "9") (pinfunction "9_9") (pintype "passive"))
      (node (ref "T27") (pin "C") (pinfunction "C_C") (pintype "passive"))
    )
    (net (code "197") (name "Net-(SV2-Pad10)") (class "Default")
      (node (ref "SV2") (pin "10") (pinfunction "10_10") (pintype "passive"))
      (node (ref "T28") (pin "C") (pinfunction "C_C") (pintype "passive"))
    )
    (net (code "198") (name "Net-(SV2-Pad11)") (class "Default")
      (node (ref "SV2") (pin "11") (pinfunction "11_11") (pintype "passive"))
      (node (ref "T25") (pin "C") (pinfunction "C_C") (pintype "passive"))
    )
    (net (code "199") (name "Net-(SV2-Pad12)") (class "Default")
      (node (ref "SV2") (pin "12") (pinfunction "12_12") (pintype "passive"))
      (node (ref "T26") (pin "C") (pinfunction "C_C") (pintype "passive"))
    )
    (net (code "200") (name "Net-(SV2-Pad15)") (class "Default")
      (node (ref "SV2") (pin "15") (pinfunction "15_15") (pintype "passive"))
      (node (ref "T47") (pin "C") (pinfunction "C_C") (pintype "passive"))
    )
    (net (code "201") (name "Net-(SV2-Pad16)") (class "Default")
      (node (ref "SV2") (pin "16") (pinfunction "16_16") (pintype "passive"))
      (node (ref "T48") (pin "C") (pinfunction "C_C") (pintype "passive"))
    )
    (net (code "202") (name "Net-(SV2-Pad17)") (class "Default")
      (node (ref "SV2") (pin "17") (pinfunction "17_17") (pintype "passive"))
      (node (ref "T45") (pin "C") (pinfunction "C_C") (pintype "passive"))
    )
    (net (code "203") (name "Net-(SV2-Pad18)") (class "Default")
      (node (ref "SV2") (pin "18") (pinfunction "18_18") (pintype "passive"))
      (node (ref "T46") (pin "C") (pinfunction "C_C") (pintype "passive"))
    )
    (net (code "204") (name "Net-(SV2-Pad19)") (class "Default")
      (node (ref "SV2") (pin "19") (pinfunction "19_19") (pintype "passive"))
      (node (ref "T44") (pin "C") (pinfunction "C_C") (pintype "passive"))
    )
    (net (code "205") (name "Net-(SV2-Pad20)") (class "Default")
      (node (ref "SV2") (pin "20") (pinfunction "20_20") (pintype "passive"))
      (node (ref "T37") (pin "C") (pinfunction "C_C") (pintype "passive"))
    )
    (net (code "206") (name "Net-(SV2-Pad21)") (class "Default")
      (node (ref "SV2") (pin "21") (pinfunction "21_21") (pintype "passive"))
      (node (ref "T43") (pin "C") (pinfunction "C_C") (pintype "passive"))
    )
    (net (code "207") (name "Net-(SV2-Pad22)") (class "Default")
      (node (ref "SV2") (pin "22") (pinfunction "22_22") (pintype "passive"))
      (node (ref "T38") (pin "C") (pinfunction "C_C") (pintype "passive"))
    )
    (net (code "208") (name "Net-(SV2-Pad23)") (class "Default")
      (node (ref "SV2") (pin "23") (pinfunction "23_23") (pintype "passive"))
      (node (ref "T42") (pin "C") (pinfunction "C_C") (pintype "passive"))
    )
    (net (code "209") (name "Net-(SV2-Pad24)") (class "Default")
      (node (ref "SV2") (pin "24") (pinfunction "24_24") (pintype "passive"))
      (node (ref "T39") (pin "C") (pinfunction "C_C") (pintype "passive"))
    )
    (net (code "210") (name "Net-(SV2-Pad25)") (class "Default")
      (node (ref "SV2") (pin "25") (pinfunction "25_25") (pintype "passive"))
      (node (ref "T41") (pin "C") (pinfunction "C_C") (pintype "passive"))
    )
    (net (code "211") (name "Net-(SV2-Pad26)") (class "Default")
      (node (ref "SV2") (pin "26") (pinfunction "26_26") (pintype "passive"))
      (node (ref "T40") (pin "C") (pinfunction "C_C") (pintype "passive"))
    )
    (net (code "212") (name "Net-(SV3-Pad1)") (class "Default")
      (node (ref "SV3") (pin "1") (pinfunction "1_1") (pintype "passive"))
      (node (ref "T59") (pin "C") (pinfunction "C_C") (pintype "passive"))
    )
    (net (code "213") (name "Net-(SV3-Pad2)") (class "Default")
      (node (ref "SV3") (pin "2") (pinfunction "2_2") (pintype "passive"))
      (node (ref "T60") (pin "C") (pinfunction "C_C") (pintype "passive"))
    )
    (net (code "214") (name "Net-(SV3-Pad3)") (class "Default")
      (node (ref "SV3") (pin "3") (pinfunction "3_3") (pintype "passive"))
      (node (ref "T57") (pin "C") (pinfunction "C_C") (pintype "passive"))
    )
    (net (code "215") (name "Net-(SV3-Pad4)") (class "Default")
      (node (ref "SV3") (pin "4") (pinfunction "4_4") (pintype "passive"))
      (node (ref "T58") (pin "C") (pinfunction "C_C") (pintype "passive"))
    )
    (net (code "216") (name "Net-(SV3-Pad5)") (class "Default")
      (node (ref "SV3") (pin "5") (pinfunction "5_5") (pintype "passive"))
      (node (ref "T55") (pin "C") (pinfunction "C_C") (pintype "passive"))
    )
    (net (code "217") (name "Net-(SV3-Pad6)") (class "Default")
      (node (ref "SV3") (pin "6") (pinfunction "6_6") (pintype "passive"))
      (node (ref "T56") (pin "C") (pinfunction "C_C") (pintype "passive"))
    )
    (net (code "218") (name "Net-(SV3-Pad7)") (class "Default")
      (node (ref "SV3") (pin "7") (pinfunction "7_7") (pintype "passive"))
      (node (ref "T53") (pin "C") (pinfunction "C_C") (pintype "passive"))
    )
    (net (code "219") (name "Net-(SV3-Pad8)") (class "Default")
      (node (ref "SV3") (pin "8") (pinfunction "8_8") (pintype "passive"))
      (node (ref "T54") (pin "C") (pinfunction "C_C") (pintype "passive"))
    )
    (net (code "220") (name "Net-(SV3-Pad9)") (class "Default")
      (node (ref "SV3") (pin "9") (pinfunction "9_9") (pintype "passive"))
      (node (ref "T51") (pin "C") (pinfunction "C_C") (pintype "passive"))
    )
    (net (code "221") (name "Net-(SV3-Pad10)") (class "Default")
      (node (ref "SV3") (pin "10") (pinfunction "10_10") (pintype "passive"))
      (node (ref "T52") (pin "C") (pinfunction "C_C") (pintype "passive"))
    )
    (net (code "222") (name "Net-(SV3-Pad11)") (class "Default")
      (node (ref "SV3") (pin "11") (pinfunction "11_11") (pintype "passive"))
      (node (ref "T49") (pin "C") (pinfunction "C_C") (pintype "passive"))
    )
    (net (code "223") (name "Net-(SV3-Pad12)") (class "Default")
      (node (ref "SV3") (pin "12") (pinfunction "12_12") (pintype "passive"))
      (node (ref "T50") (pin "C") (pinfunction "C_C") (pintype "passive"))
    )
    (net (code "224") (name "Net-(SV3-Pad15)") (class "Default")
      (node (ref "SV3") (pin "15") (pinfunction "15_15") (pintype "passive"))
      (node (ref "T71") (pin "C") (pinfunction "C_C") (pintype "passive"))
    )
    (net (code "225") (name "Net-(SV3-Pad16)") (class "Default")
      (node (ref "SV3") (pin "16") (pinfunction "16_16") (pintype "passive"))
      (node (ref "T72") (pin "C") (pinfunction "C_C") (pintype "passive"))
    )
    (net (code "226") (name "Net-(SV3-Pad17)") (class "Default")
      (node (ref "SV3") (pin "17") (pinfunction "17_17") (pintype "passive"))
      (node (ref "T69") (pin "C") (pinfunction "C_C") (pintype "passive"))
    )
    (net (code "227") (name "Net-(SV3-Pad18)") (class "Default")
      (node (ref "SV3") (pin "18") (pinfunction "18_18") (pintype "passive"))
      (node (ref "T70") (pin "C") (pinfunction "C_C") (pintype "passive"))
    )
    (net (code "228") (name "Net-(SV3-Pad19)") (class "Default")
      (node (ref "SV3") (pin "19") (pinfunction "19_19") (pintype "passive"))
      (node (ref "T68") (pin "C") (pinfunction "C_C") (pintype "passive"))
    )
    (net (code "229") (name "Net-(SV3-Pad20)") (class "Default")
      (node (ref "SV3") (pin "20") (pinfunction "20_20") (pintype "passive"))
      (node (ref "T61") (pin "C") (pinfunction "C_C") (pintype "passive"))
    )
    (net (code "230") (name "Net-(SV3-Pad21)") (class "Default")
      (node (ref "SV3") (pin "21") (pinfunction "21_21") (pintype "passive"))
      (node (ref "T67") (pin "C") (pinfunction "C_C") (pintype "passive"))
    )
    (net (code "231") (name "Net-(SV3-Pad22)") (class "Default")
      (node (ref "SV3") (pin "22") (pinfunction "22_22") (pintype "passive"))
      (node (ref "T62") (pin "C") (pinfunction "C_C") (pintype "passive"))
    )
    (net (code "232") (name "Net-(SV3-Pad23)") (class "Default")
      (node (ref "SV3") (pin "23") (pinfunction "23_23") (pintype "passive"))
      (node (ref "T66") (pin "C") (pinfunction "C_C") (pintype "passive"))
    )
    (net (code "233") (name "Net-(SV3-Pad24)") (class "Default")
      (node (ref "SV3") (pin "24") (pinfunction "24_24") (pintype "passive"))
      (node (ref "T63") (pin "C") (pinfunction "C_C") (pintype "passive"))
    )
    (net (code "234") (name "Net-(SV3-Pad25)") (class "Default")
      (node (ref "SV3") (pin "25") (pinfunction "25_25") (pintype "passive"))
      (node (ref "T65") (pin "C") (pinfunction "C_C") (pintype "passive"))
    )
    (net (code "235") (name "Net-(SV3-Pad26)") (class "Default")
      (node (ref "SV3") (pin "26") (pinfunction "26_26") (pintype "passive"))
      (node (ref "T64") (pin "C") (pinfunction "C_C") (pintype "passive"))
    )
    (net (code "236") (name "VCC") (class "Default")
      (node (ref "IC1") (pin "10") (pinfunction "SCL_10") (pintype "input"))
      (node (ref "IC2") (pin "10") (pinfunction "SCL_10") (pintype "input"))
      (node (ref "IC3") (pin "10") (pinfunction "SCL_10") (pintype "input"))
      (node (ref "IC4") (pin "10") (pinfunction "SCL_10") (pintype "input"))
      (node (ref "IC5") (pin "10") (pinfunction "SCL_10") (pintype "input"))
      (node (ref "IC6") (pin "10") (pinfunction "SCL_10") (pintype "input"))
      (node (ref "IC7") (pin "10") (pinfunction "SCL_10") (pintype "input"))
      (node (ref "IC8") (pin "10") (pinfunction "SCL_10") (pintype "input"))
      (node (ref "IC9") (pin "10") (pinfunction "SCL_10") (pintype "input"))
      (node (ref "J2") (pin "3") (pinfunction "S_3") (pintype "passive"))
    )
    (net (code "237") (name "unconnected-(IC9A-QH*-Pad9)") (class "Default")
      (node (ref "IC9") (pin "9") (pinfunction "QH*_9") (pintype "tri_state"))
    )
  )
)
